# TK90X.net
KiCad netlist of a schematic drawn in EAGLE
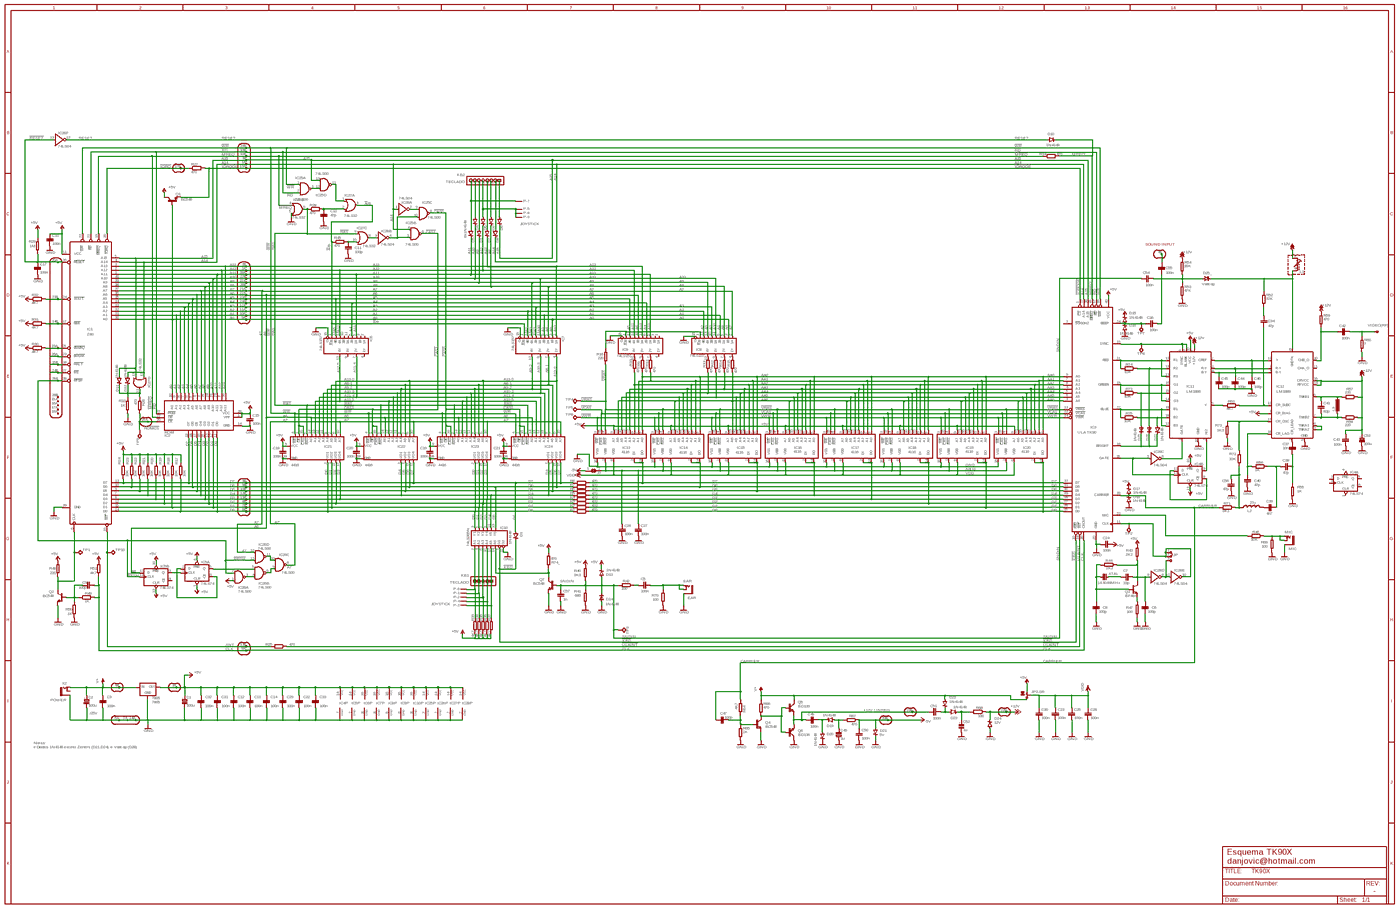
[diagram p0: schematic, sheet 1, overview]
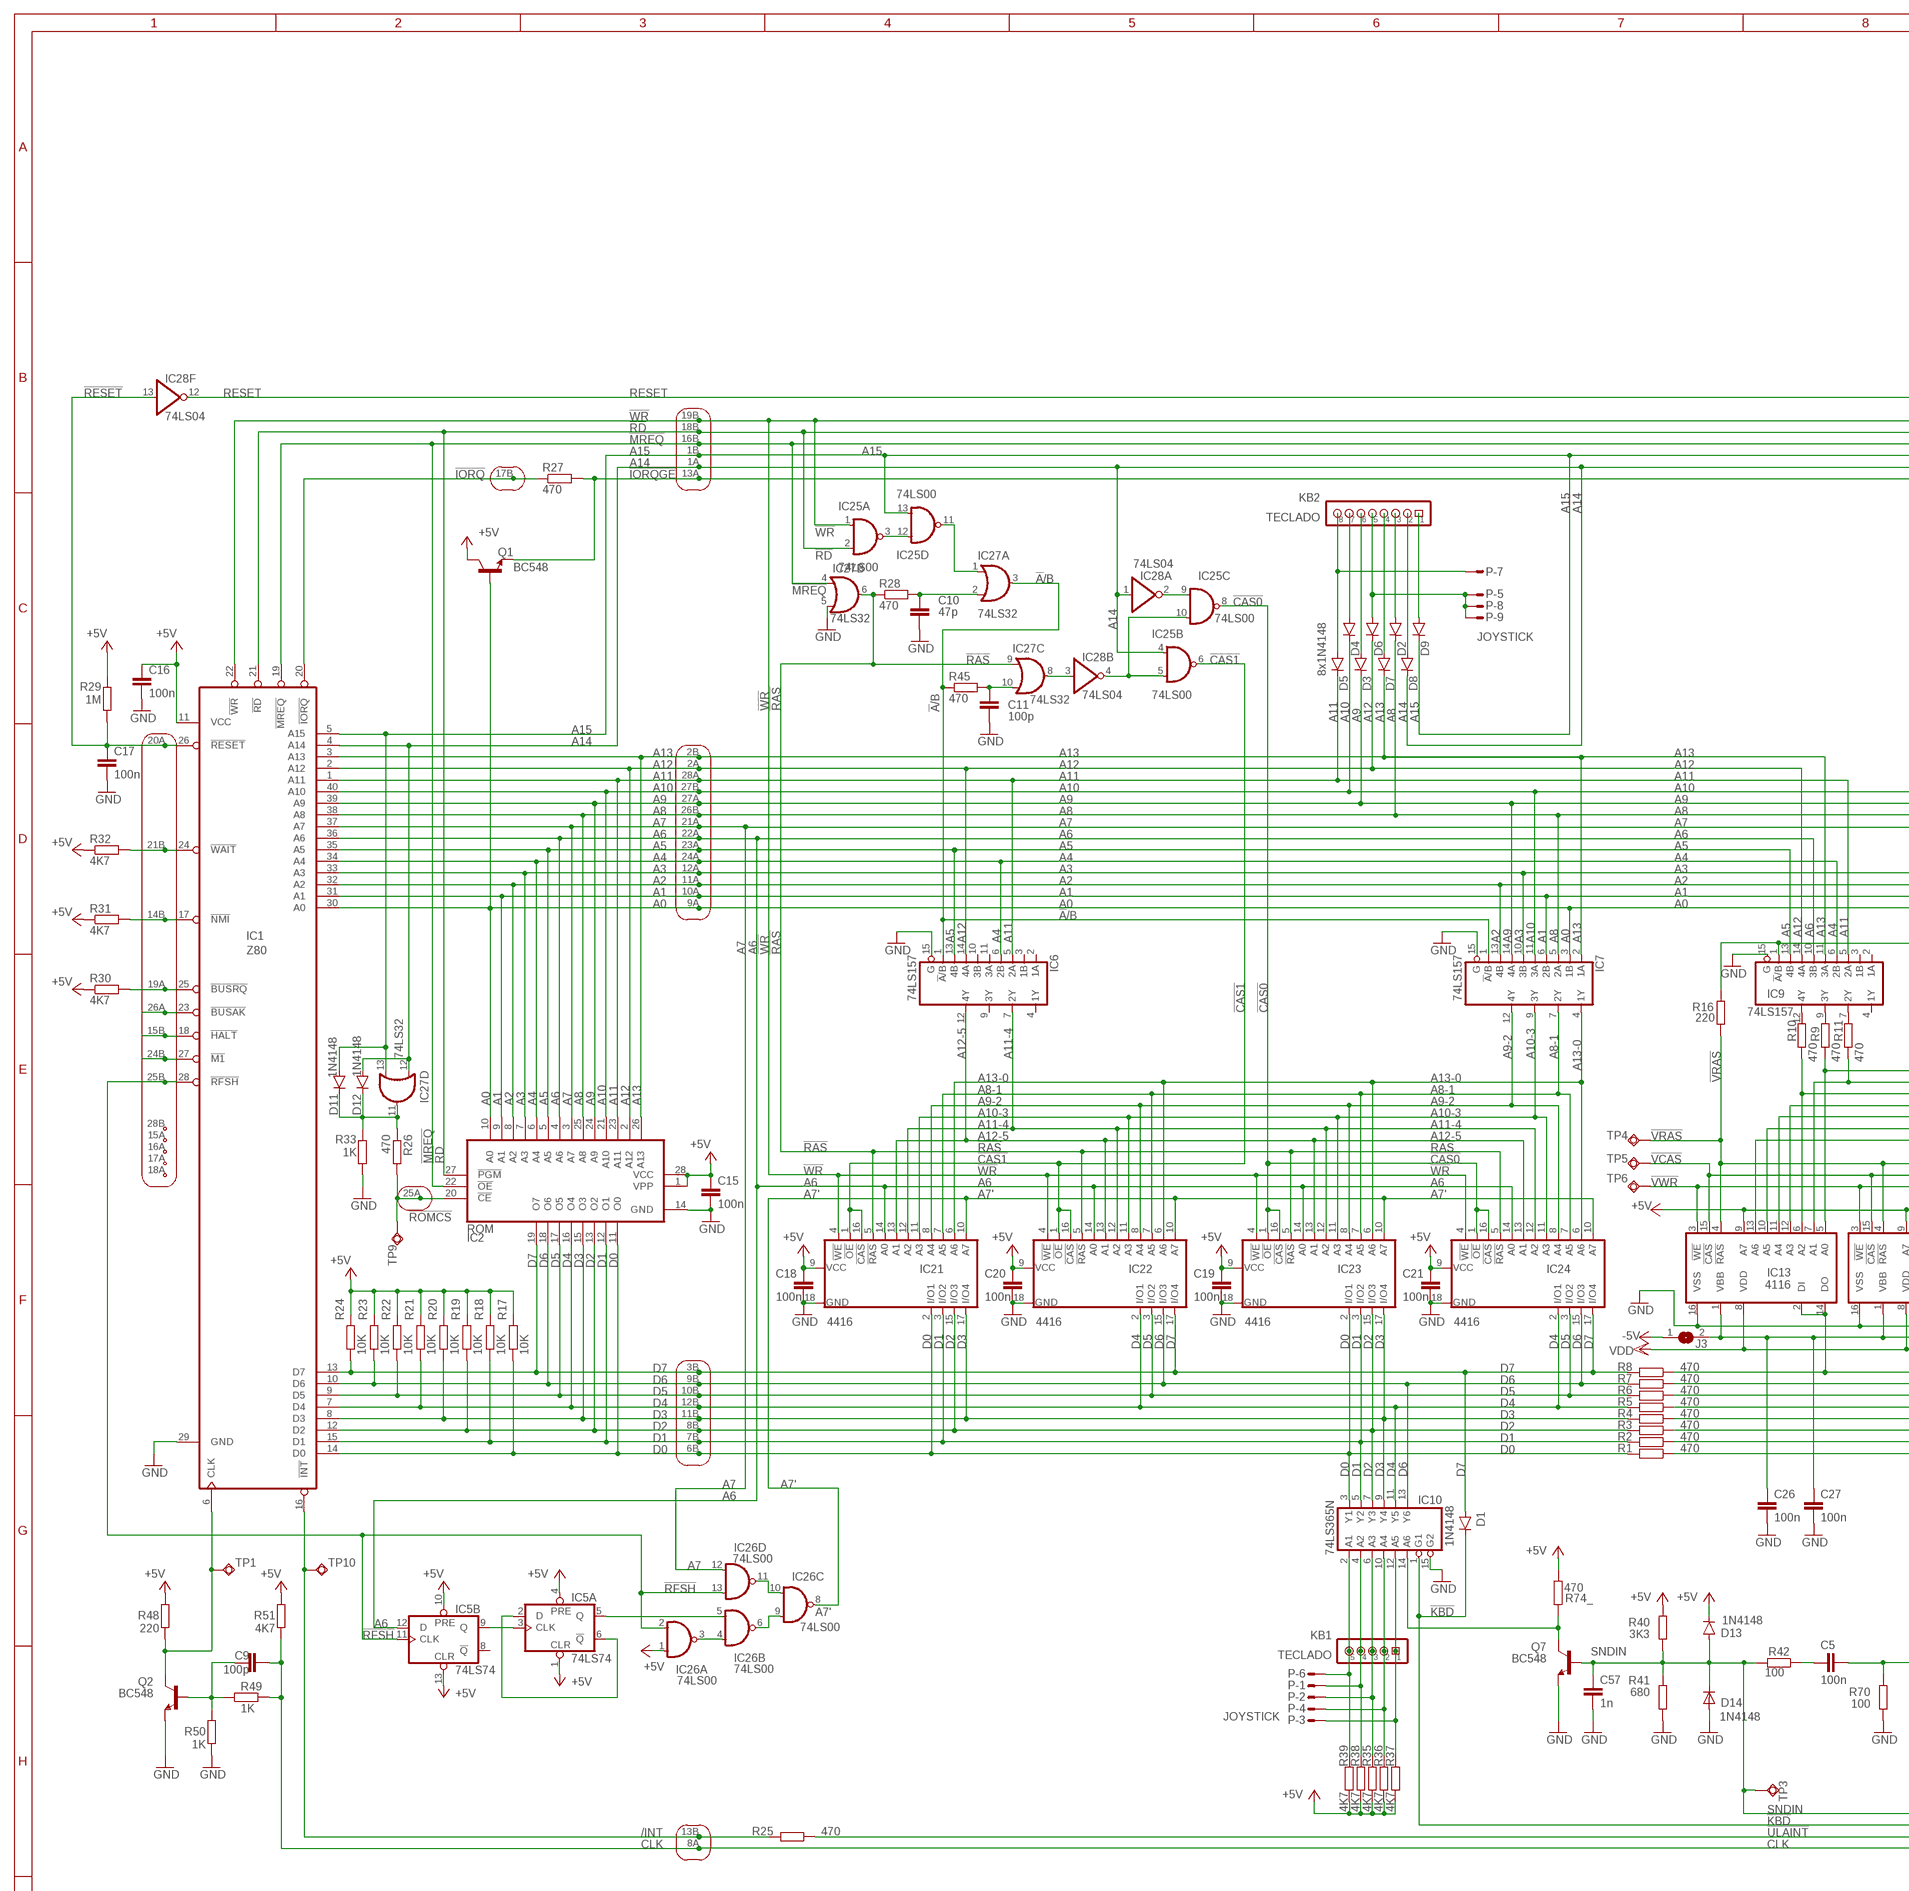
[diagram p1: schematic, sheet 1, part 1 of 4]
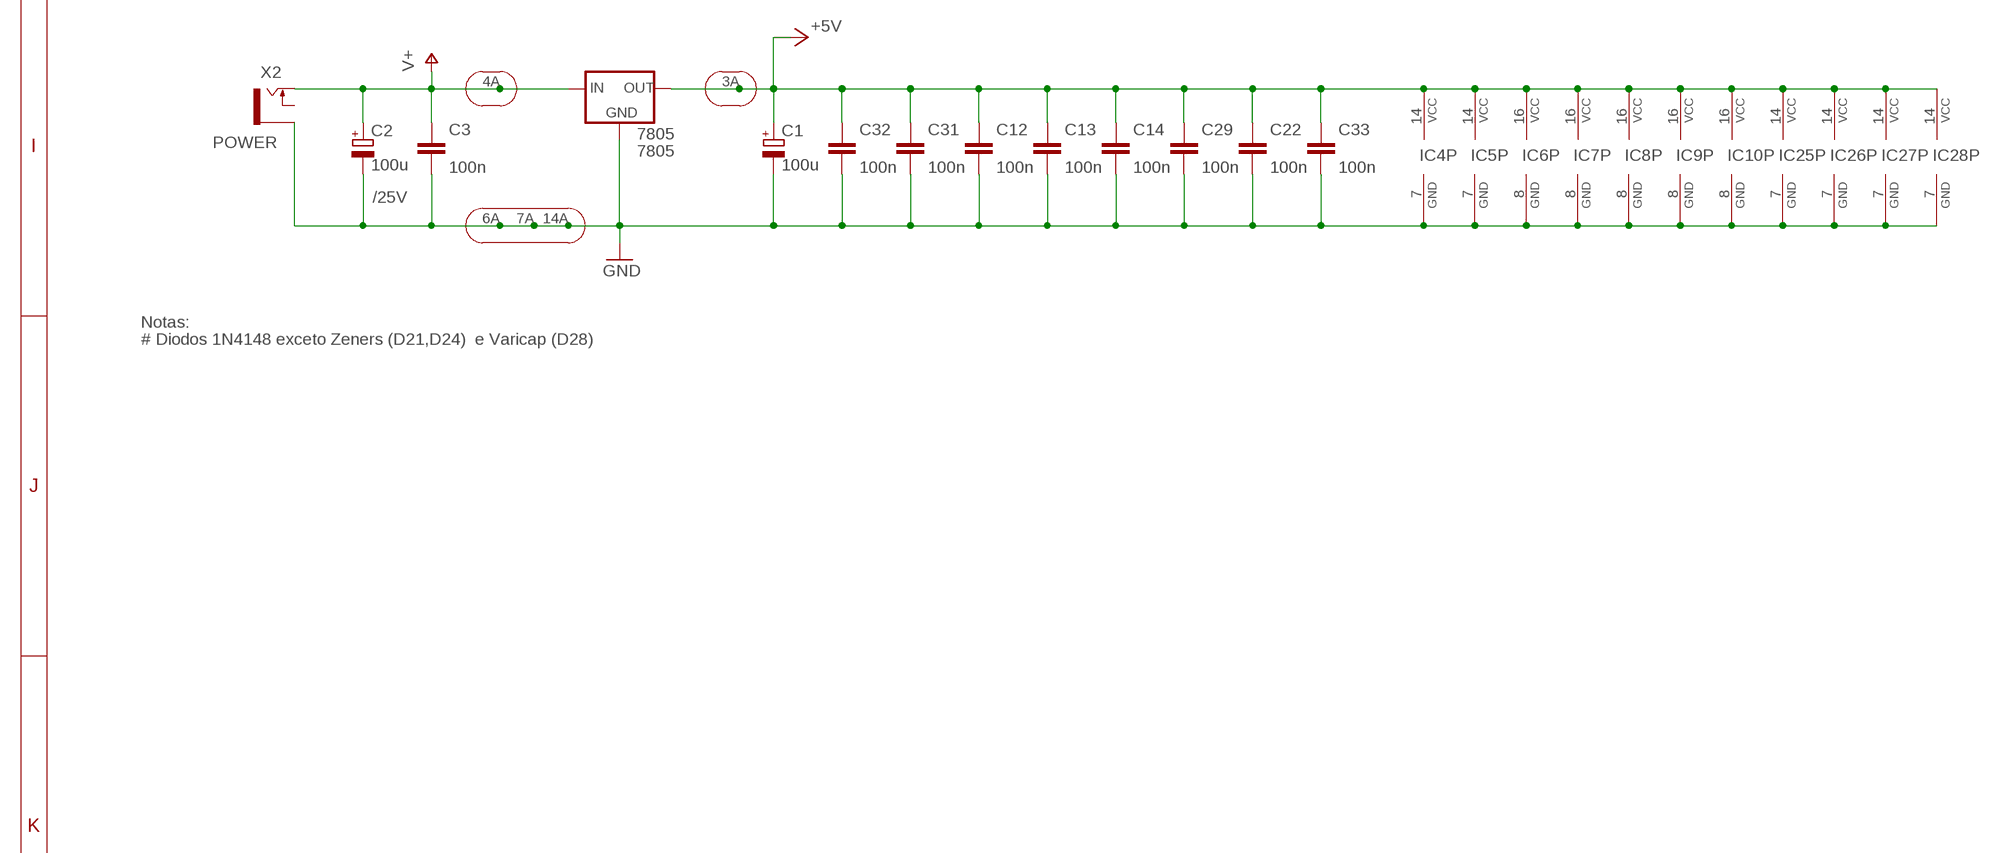
[diagram p2: schematic, sheet 1, part 2 of 4]
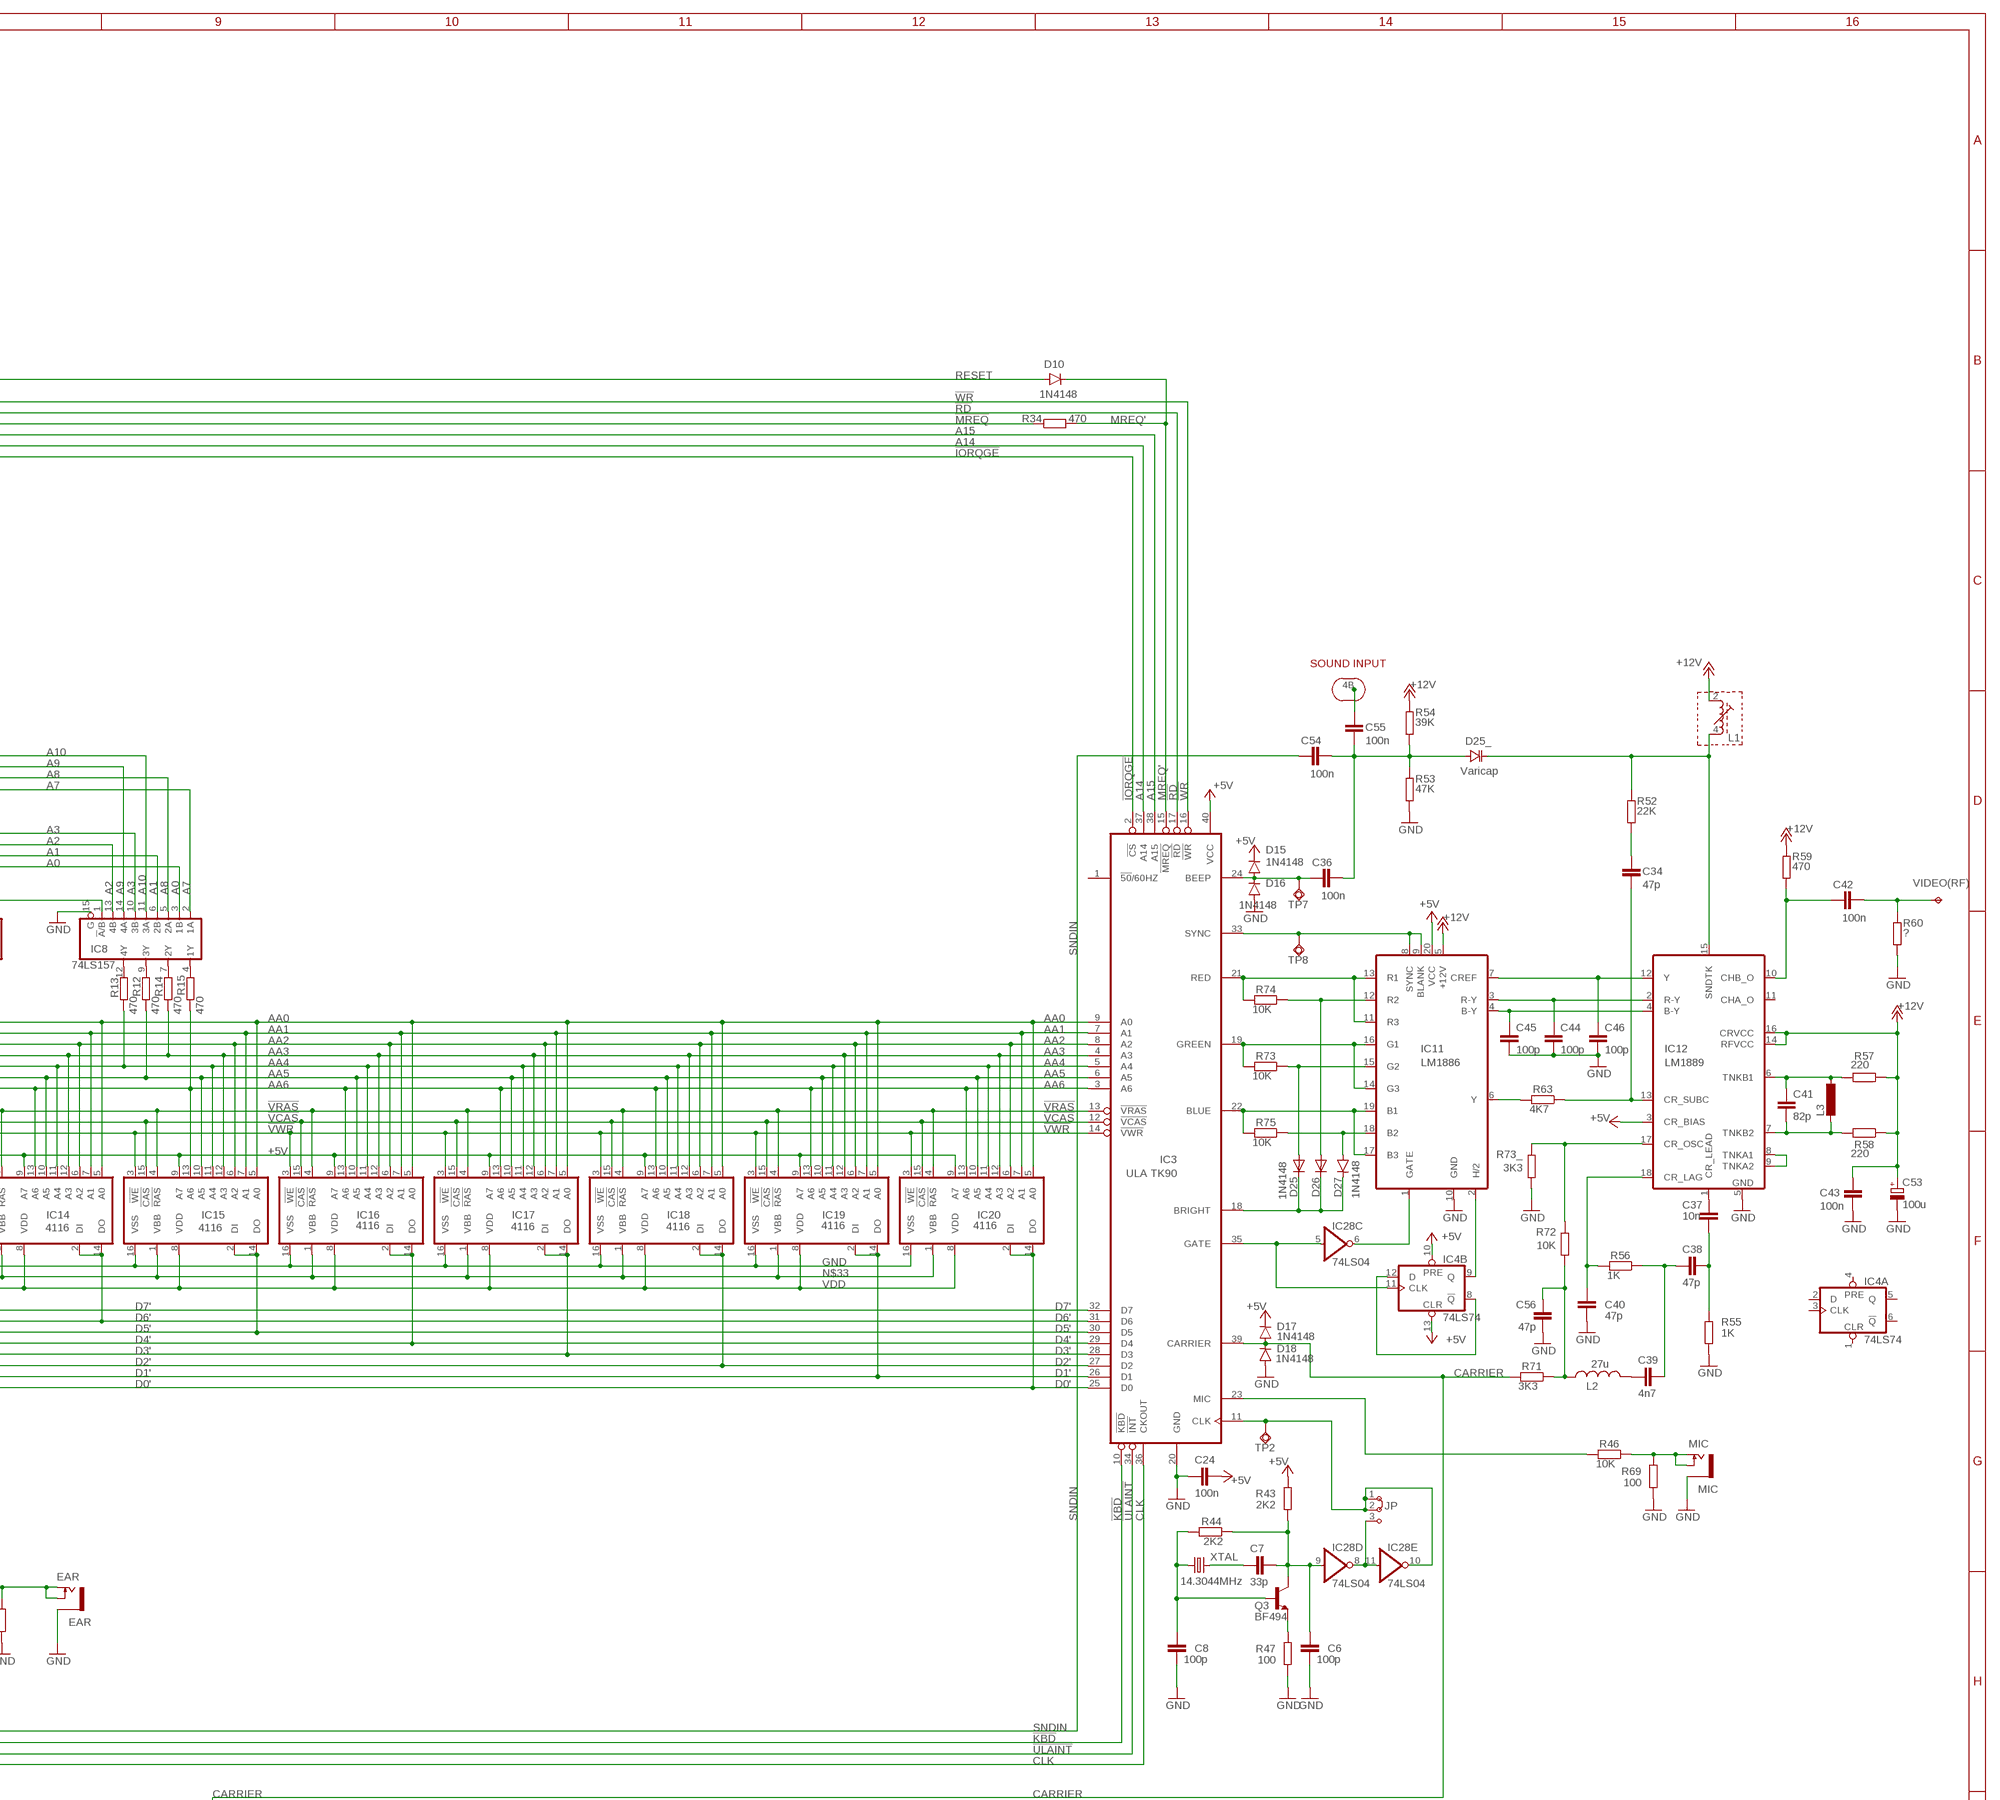
[diagram p3: schematic, sheet 1, part 3 of 4]
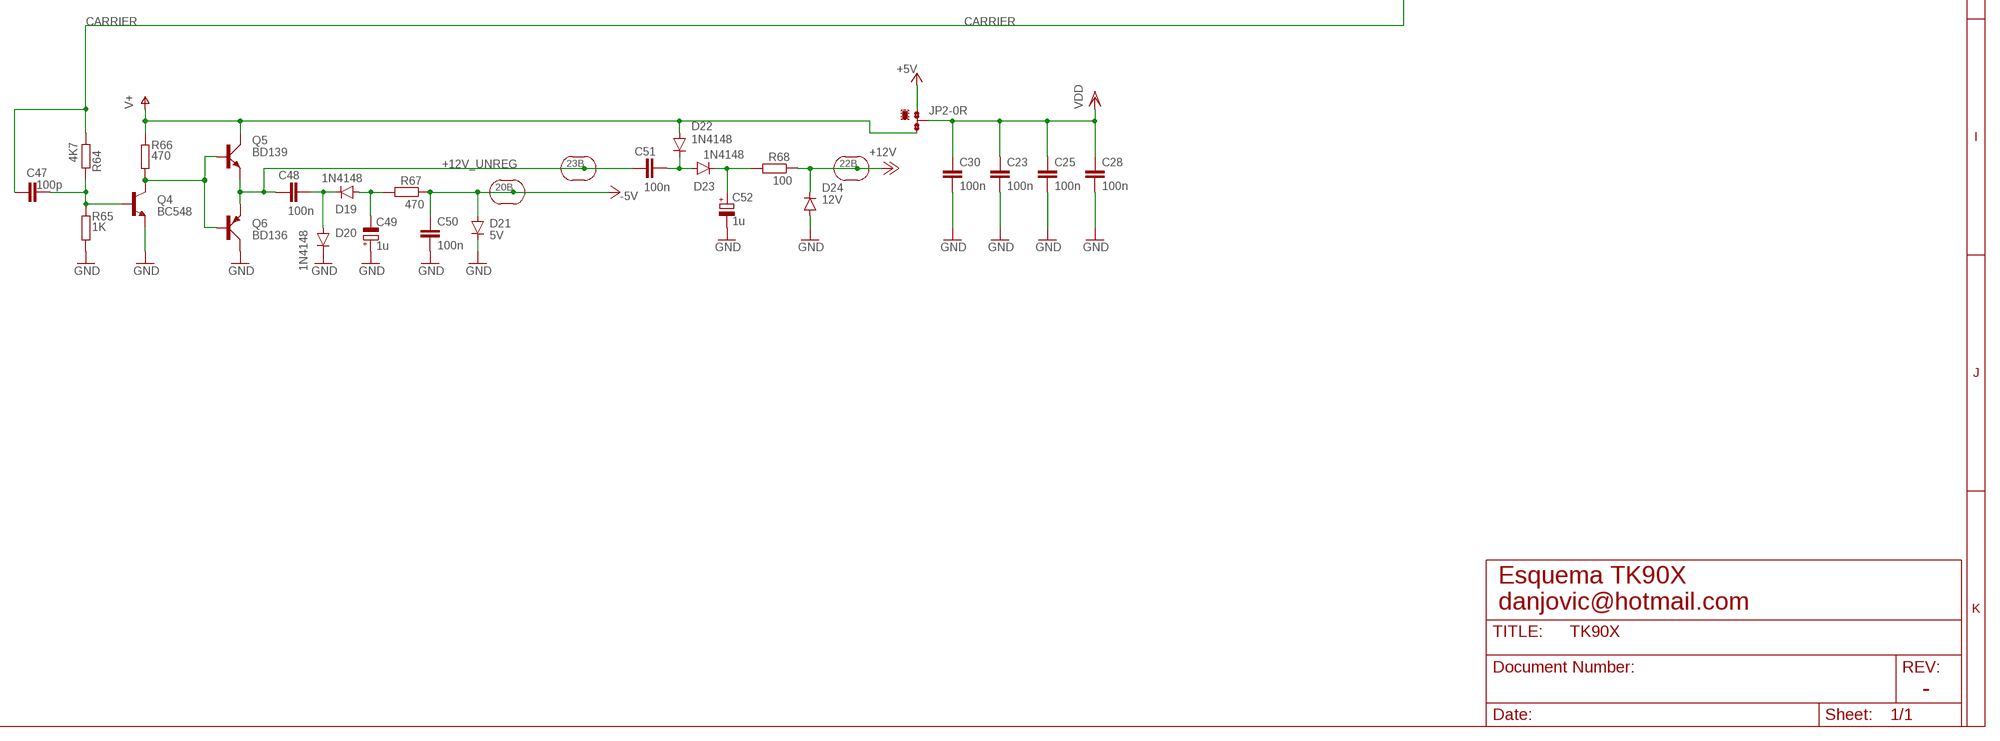
[diagram p4: schematic, sheet 1, part 4 of 4]

(export (version "E")
  (design (tool "Eeschema 10.0.6"))
  (components
    (comp (ref "7805")
      (value "7805")
      (footprint "eagle-import:78XXL")
      (libsource (lib "eagle-import") (part "78XXL"))
    )
    (comp (ref "C1")
      (value "100u")
      (footprint "eagle-import:E5-8,5")
      (libsource (lib "eagle-import") (part "CPOL-EUE5-8.5"))
    )
    (comp (ref "C2")
      (value "100u")
      (footprint "eagle-import:E5-8,5")
      (libsource (lib "eagle-import") (part "CPOL-EUE5-8.5"))
    )
    (comp (ref "C3")
      (value "100n")
      (footprint "eagle-import:C050-024X044")
      (libsource (lib "eagle-import") (part "C-EU050-024X044"))
    )
    (comp (ref "C5")
      (value "100n")
      (footprint "eagle-import:C050-024X044")
      (libsource (lib "eagle-import") (part "C-EU050-024X044"))
    )
    (comp (ref "C6")
      (value "100p")
      (footprint "eagle-import:C050-024X044")
      (libsource (lib "eagle-import") (part "C-EU050-024X044"))
    )
    (comp (ref "C7")
      (value "33p")
      (footprint "eagle-import:C050-024X044")
      (libsource (lib "eagle-import") (part "C-EU050-024X044"))
    )
    (comp (ref "C8")
      (value "100p")
      (footprint "eagle-import:C050-024X044")
      (libsource (lib "eagle-import") (part "C-EU050-024X044"))
    )
    (comp (ref "C9")
      (value "100p")
      (footprint "eagle-import:C050-024X044")
      (libsource (lib "eagle-import") (part "C-EU050-024X044"))
    )
    (comp (ref "C10")
      (value "47p")
      (footprint "eagle-import:C050-024X044")
      (libsource (lib "eagle-import") (part "C-EU050-024X044"))
    )
    (comp (ref "C11")
      (value "100p")
      (footprint "eagle-import:C050-024X044")
      (libsource (lib "eagle-import") (part "C-EU050-024X044"))
    )
    (comp (ref "C12")
      (value "100n")
      (footprint "eagle-import:C050-024X044")
      (libsource (lib "eagle-import") (part "C-EU050-024X044"))
    )
    (comp (ref "C13")
      (value "100n")
      (footprint "eagle-import:C050-024X044")
      (libsource (lib "eagle-import") (part "C-EU050-024X044"))
    )
    (comp (ref "C14")
      (value "100n")
      (footprint "eagle-import:C050-024X044")
      (libsource (lib "eagle-import") (part "C-EU050-024X044"))
    )
    (comp (ref "C15")
      (value "100n")
      (footprint "eagle-import:C050-024X044")
      (libsource (lib "eagle-import") (part "C-EU050-024X044"))
    )
    (comp (ref "C16")
      (value "100n")
      (footprint "eagle-import:C050-024X044")
      (libsource (lib "eagle-import") (part "C-EU050-024X044"))
    )
    (comp (ref "C17")
      (value "100n")
      (footprint "eagle-import:C050-024X044")
      (libsource (lib "eagle-import") (part "C-EU050-024X044"))
    )
    (comp (ref "C18")
      (value "100n")
      (footprint "eagle-import:C050-024X044")
      (libsource (lib "eagle-import") (part "C-EU050-024X044"))
    )
    (comp (ref "C19")
      (value "100n")
      (footprint "eagle-import:C050-024X044")
      (libsource (lib "eagle-import") (part "C-EU050-024X044"))
    )
    (comp (ref "C20")
      (value "100n")
      (footprint "eagle-import:C050-024X044")
      (libsource (lib "eagle-import") (part "C-EU050-024X044"))
    )
    (comp (ref "C21")
      (value "100n")
      (footprint "eagle-import:C050-024X044")
      (libsource (lib "eagle-import") (part "C-EU050-024X044"))
    )
    (comp (ref "C22")
      (value "100n")
      (footprint "eagle-import:C050-024X044")
      (libsource (lib "eagle-import") (part "C-EU050-024X044"))
    )
    (comp (ref "C23")
      (value "100n")
      (footprint "eagle-import:C050-024X044")
      (libsource (lib "eagle-import") (part "C-EU050-024X044"))
    )
    (comp (ref "C24")
      (value "100n")
      (footprint "eagle-import:C050-024X044")
      (libsource (lib "eagle-import") (part "C-EU050-024X044"))
    )
    (comp (ref "C25")
      (value "100n")
      (footprint "eagle-import:C050-024X044")
      (libsource (lib "eagle-import") (part "C-EU050-024X044"))
    )
    (comp (ref "C26")
      (value "100n")
      (footprint "eagle-import:C050-024X044")
      (libsource (lib "eagle-import") (part "C-EU050-024X044"))
    )
    (comp (ref "C27")
      (value "100n")
      (footprint "eagle-import:C050-024X044")
      (libsource (lib "eagle-import") (part "C-EU050-024X044"))
    )
    (comp (ref "C28")
      (value "100n")
      (footprint "eagle-import:C050-024X044")
      (libsource (lib "eagle-import") (part "C-EU050-024X044"))
    )
    (comp (ref "C29")
      (value "100n")
      (footprint "eagle-import:C050-024X044")
      (libsource (lib "eagle-import") (part "C-EU050-024X044"))
    )
    (comp (ref "C30")
      (value "100n")
      (footprint "eagle-import:C050-024X044")
      (libsource (lib "eagle-import") (part "C-EU050-024X044"))
    )
    (comp (ref "C31")
      (value "100n")
      (footprint "eagle-import:C050-024X044")
      (libsource (lib "eagle-import") (part "C-EU050-024X044"))
    )
    (comp (ref "C32")
      (value "100n")
      (footprint "eagle-import:C050-024X044")
      (libsource (lib "eagle-import") (part "C-EU050-024X044"))
    )
    (comp (ref "C33")
      (value "100n")
      (footprint "eagle-import:C050-024X044")
      (libsource (lib "eagle-import") (part "C-EU050-024X044"))
    )
    (comp (ref "C34")
      (value "47p")
      (footprint "eagle-import:C050-024X044")
      (libsource (lib "eagle-import") (part "C-EU050-024X044"))
    )
    (comp (ref "C36")
      (value "100n")
      (footprint "eagle-import:C050-024X044")
      (libsource (lib "eagle-import") (part "C-EU050-024X044"))
    )
    (comp (ref "C37")
      (value "10n")
      (footprint "eagle-import:C050-024X044")
      (libsource (lib "eagle-import") (part "C-EU050-024X044"))
    )
    (comp (ref "C38")
      (value "47p")
      (footprint "eagle-import:C050-024X044")
      (libsource (lib "eagle-import") (part "C-EU050-024X044"))
    )
    (comp (ref "C39")
      (value "4n7")
      (footprint "eagle-import:C050-024X044")
      (libsource (lib "eagle-import") (part "C-EU050-024X044"))
    )
    (comp (ref "C40")
      (value "47p")
      (footprint "eagle-import:C050-024X044")
      (libsource (lib "eagle-import") (part "C-EU050-024X044"))
    )
    (comp (ref "C41")
      (value "82p")
      (footprint "eagle-import:C050-024X044")
      (libsource (lib "eagle-import") (part "C-EU050-024X044"))
    )
    (comp (ref "C42")
      (value "100n")
      (footprint "eagle-import:C050-024X044")
      (libsource (lib "eagle-import") (part "C-EU050-024X044"))
    )
    (comp (ref "C43")
      (value "100n")
      (footprint "eagle-import:C050-024X044")
      (libsource (lib "eagle-import") (part "C-EU050-024X044"))
    )
    (comp (ref "C44")
      (value "100p")
      (footprint "eagle-import:C050-024X044")
      (libsource (lib "eagle-import") (part "C-EU050-024X044"))
    )
    (comp (ref "C45")
      (value "100p")
      (footprint "eagle-import:C050-024X044")
      (libsource (lib "eagle-import") (part "C-EU050-024X044"))
    )
    (comp (ref "C46")
      (value "100p")
      (footprint "eagle-import:C050-024X044")
      (libsource (lib "eagle-import") (part "C-EU050-024X044"))
    )
    (comp (ref "C47")
      (value "100p")
      (footprint "eagle-import:C050-024X044")
      (libsource (lib "eagle-import") (part "C-EU050-024X044"))
    )
    (comp (ref "C48")
      (value "100n")
      (footprint "eagle-import:C050-024X044")
      (libsource (lib "eagle-import") (part "C-EU050-024X044"))
    )
    (comp (ref "C49")
      (value "1u")
      (footprint "eagle-import:E2-4")
      (libsource (lib "eagle-import") (part "CPOL-EUE2-4"))
    )
    (comp (ref "C50")
      (value "100n")
      (footprint "eagle-import:C050-024X044")
      (libsource (lib "eagle-import") (part "C-EU050-024X044"))
    )
    (comp (ref "C51")
      (value "100n")
      (footprint "eagle-import:C050-024X044")
      (libsource (lib "eagle-import") (part "C-EU050-024X044"))
    )
    (comp (ref "C52")
      (value "1u")
      (footprint "eagle-import:E2-5")
      (libsource (lib "eagle-import") (part "CPOL-EUE2-5"))
    )
    (comp (ref "C53")
      (value "100u")
      (footprint "eagle-import:E5-4")
      (libsource (lib "eagle-import") (part "CPOL-EUE5-4"))
    )
    (comp (ref "C54")
      (value "100n")
      (footprint "eagle-import:C050-024X044")
      (libsource (lib "eagle-import") (part "C-EU050-024X044"))
    )
    (comp (ref "C55")
      (value "100n")
      (footprint "eagle-import:C050-024X044")
      (libsource (lib "eagle-import") (part "C-EU050-024X044"))
    )
    (comp (ref "C56")
      (value "47p")
      (footprint "eagle-import:C050-024X044")
      (libsource (lib "eagle-import") (part "C-EU050-024X044"))
    )
    (comp (ref "C57")
      (value "1n")
      (footprint "eagle-import:C050-024X044")
      (libsource (lib "eagle-import") (part "C-EU050-024X044"))
    )
    (comp (ref "D1")
      (value "1N4148")
      (footprint "eagle-import:DO35-12")
      (libsource (lib "eagle-import") (part "DDO35-12"))
    )
    (comp (ref "D2")
      (value "1N4148")
      (footprint "eagle-import:DO35-12")
      (libsource (lib "eagle-import") (part "DDO35-12"))
    )
    (comp (ref "D3")
      (value "1N4148")
      (footprint "eagle-import:DO35-12")
      (libsource (lib "eagle-import") (part "DDO35-12"))
    )
    (comp (ref "D4")
      (value "1N4148")
      (footprint "eagle-import:DO35-12")
      (libsource (lib "eagle-import") (part "DDO35-12"))
    )
    (comp (ref "D5")
      (value "1N4148")
      (footprint "eagle-import:DO35-12")
      (libsource (lib "eagle-import") (part "DDO35-12"))
    )
    (comp (ref "D6")
      (value "1N4148")
      (footprint "eagle-import:DO35-12")
      (libsource (lib "eagle-import") (part "DDO35-12"))
    )
    (comp (ref "D7")
      (value "1N4148")
      (footprint "eagle-import:DO35-12")
      (libsource (lib "eagle-import") (part "DDO35-12"))
    )
    (comp (ref "D8")
      (value "1N4148")
      (footprint "eagle-import:DO35-12")
      (libsource (lib "eagle-import") (part "DDO35-12"))
    )
    (comp (ref "D9")
      (value "1N4148")
      (footprint "eagle-import:DO35-12")
      (libsource (lib "eagle-import") (part "DDO35-12"))
    )
    (comp (ref "D10")
      (value "1N4148")
      (footprint "eagle-import:DO35-12")
      (libsource (lib "eagle-import") (part "DDO35-12"))
    )
    (comp (ref "D11")
      (value "1N4148")
      (footprint "eagle-import:DO35-12")
      (libsource (lib "eagle-import") (part "DDO35-12"))
    )
    (comp (ref "D12")
      (value "1N4148")
      (footprint "eagle-import:DO35-12")
      (libsource (lib "eagle-import") (part "DDO35-12"))
    )
    (comp (ref "D13")
      (value "1N4148")
      (footprint "eagle-import:DO35-12")
      (libsource (lib "eagle-import") (part "DDO35-12"))
    )
    (comp (ref "D14")
      (value "1N4148")
      (footprint "eagle-import:D-5")
      (libsource (lib "eagle-import") (part "DIODE-D-5"))
    )
    (comp (ref "D15")
      (value "1N4148")
      (footprint "eagle-import:DO35-12")
      (libsource (lib "eagle-import") (part "DDO35-12"))
    )
    (comp (ref "D16")
      (value "1N4148")
      (footprint "eagle-import:DO35-12")
      (libsource (lib "eagle-import") (part "DDO35-12"))
    )
    (comp (ref "D17")
      (value "1N4148")
      (footprint "eagle-import:DO35-12")
      (libsource (lib "eagle-import") (part "DDO35-12"))
    )
    (comp (ref "D18")
      (value "1N4148")
      (footprint "eagle-import:DO35-12")
      (libsource (lib "eagle-import") (part "DDO35-12"))
    )
    (comp (ref "D19")
      (value "1N4148")
      (footprint "eagle-import:DO35-12")
      (libsource (lib "eagle-import") (part "DDO35-12"))
    )
    (comp (ref "D20")
      (value "1N4148")
      (footprint "eagle-import:DO35-12")
      (libsource (lib "eagle-import") (part "DDO35-12"))
    )
    (comp (ref "D21")
      (value "5V")
      (footprint "eagle-import:DO35-12")
      (libsource (lib "eagle-import") (part "DDO35-12"))
    )
    (comp (ref "D22")
      (value "1N4148")
      (footprint "eagle-import:DO35-12")
      (libsource (lib "eagle-import") (part "DDO35-12"))
    )
    (comp (ref "D23")
      (value "1N4148")
      (footprint "eagle-import:DO35-12")
      (libsource (lib "eagle-import") (part "DDO35-12"))
    )
    (comp (ref "D24")
      (value "12V")
      (footprint "eagle-import:DO35-12")
      (libsource (lib "eagle-import") (part "DDO35-12"))
    )
    (comp (ref "D25")
      (value "1N4148")
      (footprint "eagle-import:D-5")
      (libsource (lib "eagle-import") (part "DIODE-D-5"))
    )
    (comp (ref "D25_")
      (value "Varicap")
      (footprint "eagle-import:D200")
      (libsource (lib "eagle-import") (part "VARICAP-200"))
    )
    (comp (ref "D26")
      (value "1N4148")
      (footprint "eagle-import:D-5")
      (libsource (lib "eagle-import") (part "DIODE-D-5"))
    )
    (comp (ref "D27")
      (value "1N4148")
      (footprint "eagle-import:DO35-12")
      (libsource (lib "eagle-import") (part "DDO35-12"))
    )
    (comp (ref "EAR")
      (value "EAR")
      (footprint "eagle-import:MONO")
      (libsource (lib "eagle-import") (part "JACK?-MONO"))
    )
    (comp (ref "IC1")
      (value "Z80")
      (footprint "eagle-import:DIL40")
      (libsource (lib "eagle-import") (part "Z80CPU"))
    )
    (comp (ref "IC2")
      (value "ROM")
      (footprint "eagle-import:DIL28")
      (libsource (lib "eagle-import") (part "25128"))
    )
    (comp (ref "IC3")
      (value "ULA TK90")
      (footprint "eagle-import:DIL40")
      (libsource (lib "eagle-import") (part "ULA-TK90"))
    )
    (comp (ref "IC4")
      (value "74LS74")
      (footprint "eagle-import:DIL14")
      (libsource (lib "eagle-import") (part "7474NLS"))
    )
    (comp (ref "IC5")
      (value "74LS74")
      (footprint "eagle-import:DIL14")
      (libsource (lib "eagle-import") (part "7474NLS"))
    )
    (comp (ref "IC6")
      (value "74LS157")
      (footprint "eagle-import:DIL16")
      (libsource (lib "eagle-import") (part "74157NS"))
    )
    (comp (ref "IC7")
      (value "74LS157")
      (footprint "eagle-import:DIL16")
      (libsource (lib "eagle-import") (part "74157NS"))
    )
    (comp (ref "IC8")
      (value "74LS157")
      (footprint "eagle-import:DIL16")
      (libsource (lib "eagle-import") (part "74157NS"))
    )
    (comp (ref "IC9")
      (value "74LS157")
      (footprint "eagle-import:DIL16")
      (libsource (lib "eagle-import") (part "74157NS"))
    )
    (comp (ref "IC10")
      (value "74LS365N")
      (footprint "eagle-import:DIL16")
      (libsource (lib "eagle-import") (part "74365NLS"))
    )
    (comp (ref "IC11")
      (value "LM1886")
      (footprint "eagle-import:DIL20")
      (libsource (lib "eagle-import") (part "LM1886N"))
    )
    (comp (ref "IC12")
      (value "LM1889")
      (footprint "eagle-import:DIL18")
      (libsource (lib "eagle-import") (part "LM1889"))
    )
    (comp (ref "IC13")
      (value "4116")
      (footprint "eagle-import:DIL16")
      (libsource (lib "eagle-import") (part "MK4516"))
    )
    (comp (ref "IC14")
      (value "4116")
      (footprint "eagle-import:DIL16")
      (libsource (lib "eagle-import") (part "MK4516"))
    )
    (comp (ref "IC15")
      (value "4116")
      (footprint "eagle-import:DIL16")
      (libsource (lib "eagle-import") (part "MK4516"))
    )
    (comp (ref "IC16")
      (value "4116")
      (footprint "eagle-import:DIL16")
      (libsource (lib "eagle-import") (part "MK4516"))
    )
    (comp (ref "IC17")
      (value "4116")
      (footprint "eagle-import:DIL16")
      (libsource (lib "eagle-import") (part "MK4516"))
    )
    (comp (ref "IC18")
      (value "4116")
      (footprint "eagle-import:DIL16")
      (libsource (lib "eagle-import") (part "MK4516"))
    )
    (comp (ref "IC19")
      (value "4116")
      (footprint "eagle-import:DIL16")
      (libsource (lib "eagle-import") (part "MK4516"))
    )
    (comp (ref "IC20")
      (value "4116")
      (footprint "eagle-import:DIL16")
      (libsource (lib "eagle-import") (part "MK4516"))
    )
    (comp (ref "IC21")
      (value "4416")
      (footprint "eagle-import:DIL18")
      (libsource (lib "eagle-import") (part "4416"))
    )
    (comp (ref "IC22")
      (value "4416")
      (footprint "eagle-import:DIL18")
      (libsource (lib "eagle-import") (part "4416"))
    )
    (comp (ref "IC23")
      (value "4416")
      (footprint "eagle-import:DIL18")
      (libsource (lib "eagle-import") (part "4416"))
    )
    (comp (ref "IC24")
      (value "4416")
      (footprint "eagle-import:DIL18")
      (libsource (lib "eagle-import") (part "4416"))
    )
    (comp (ref "IC25")
      (value "74LS00")
      (footprint "eagle-import:DIL14")
      (libsource (lib "eagle-import") (part "7400NLS"))
    )
    (comp (ref "IC26")
      (value "74LS00")
      (footprint "eagle-import:DIL14")
      (libsource (lib "eagle-import") (part "7400NLS"))
    )
    (comp (ref "IC27")
      (value "74LS32")
      (footprint "eagle-import:DIL14")
      (libsource (lib "eagle-import") (part "7432NLS"))
    )
    (comp (ref "IC28")
      (value "74LS04")
      (footprint "eagle-import:DIL14")
      (libsource (lib "eagle-import") (part "7404NLS"))
    )
    (comp (ref "J3") (value "SJ") (footprint "eagle-import:SJ") (libsource (lib "eagle-import") (part "SJ")))
    (comp (ref "JP")
      (value "J2X1MM")
      (footprint "eagle-import:03C")
      (libsource (lib "eagle-import") (part "J2X1MM"))
    )
    (comp (ref "JP2")
      (value "0R-JUMPB")
      (footprint "eagle-import:B0R-JMP")
      (libsource (lib "eagle-import") (part "0R-JUMPB"))
    )
    (comp (ref "KB1")
      (value "TECLADO")
      (footprint "eagle-import:FE05-1")
      (libsource (lib "eagle-import") (part "CON-TECL-5"))
    )
    (comp (ref "KB2")
      (value "TECLADO")
      (footprint "eagle-import:FE08")
      (libsource (lib "eagle-import") (part "CON-TECL-8"))
    )
    (comp (ref "L1")
      (value "COIL")
      (footprint "eagle-import:COIL")
      (libsource (lib "eagle-import") (part "COIL"))
    )
    (comp (ref "L2")
      (value "27u")
      (footprint "eagle-import:0207_7")
      (libsource (lib "eagle-import") (part "L-US0207/7"))
    )
    (comp (ref "L3")
      (value "L-EU0204/5")
      (footprint "eagle-import:0204_5")
      (libsource (lib "eagle-import") (part "L-EU0204/5"))
    )
    (comp (ref "MIC")
      (value "MIC")
      (footprint "eagle-import:MONO")
      (libsource (lib "eagle-import") (part "JACK?-MONO"))
    )
    (comp (ref "P")
      (value "JOYSTICK")
      (footprint "eagle-import:177-009-MALE")
      (libsource (lib "eagle-import") (part "M09?S.590"))
    )
    (comp (ref "Q1")
      (value "BC548")
      (footprint "eagle-import:TO92L")
      (libsource (lib "eagle-import") (part "-NPN-TO92L"))
    )
    (comp (ref "Q2")
      (value "BC548")
      (footprint "eagle-import:TO92L")
      (libsource (lib "eagle-import") (part "-NPN-TO92L"))
    )
    (comp (ref "Q3")
      (value "BF494")
      (footprint "eagle-import:TO92-CEB")
      (libsource (lib "eagle-import") (part "BF494"))
    )
    (comp (ref "Q4")
      (value "BC548")
      (footprint "eagle-import:TO92L")
      (libsource (lib "eagle-import") (part "-NPN-TO92L"))
    )
    (comp (ref "Q5")
      (value "BD139")
      (footprint "eagle-import:TO126AV")
      (libsource (lib "eagle-import") (part "BD139"))
    )
    (comp (ref "Q6")
      (value "BD136")
      (footprint "eagle-import:TO126AV")
      (libsource (lib "eagle-import") (part "BD140"))
    )
    (comp (ref "Q7")
      (value "BC548")
      (footprint "eagle-import:TO92L")
      (libsource (lib "eagle-import") (part "-NPN-TO92L"))
    )
    (comp (ref "R1")
      (value "470")
      (footprint "eagle-import:0207_12")
      (libsource (lib "eagle-import") (part "R-EU_0207/12"))
    )
    (comp (ref "R2")
      (value "470")
      (footprint "eagle-import:0207_12")
      (libsource (lib "eagle-import") (part "R-EU_0207/12"))
    )
    (comp (ref "R3")
      (value "470")
      (footprint "eagle-import:0207_12")
      (libsource (lib "eagle-import") (part "R-EU_0207/12"))
    )
    (comp (ref "R4")
      (value "470")
      (footprint "eagle-import:0207_12")
      (libsource (lib "eagle-import") (part "R-EU_0207/12"))
    )
    (comp (ref "R5")
      (value "470")
      (footprint "eagle-import:0207_12")
      (libsource (lib "eagle-import") (part "R-EU_0207/12"))
    )
    (comp (ref "R6")
      (value "470")
      (footprint "eagle-import:0207_12")
      (libsource (lib "eagle-import") (part "R-EU_0207/12"))
    )
    (comp (ref "R7")
      (value "470")
      (footprint "eagle-import:0207_12")
      (libsource (lib "eagle-import") (part "R-EU_0207/12"))
    )
    (comp (ref "R8")
      (value "470")
      (footprint "eagle-import:0207_12")
      (libsource (lib "eagle-import") (part "R-EU_0207/12"))
    )
    (comp (ref "R9")
      (value "470")
      (footprint "eagle-import:0207_12")
      (libsource (lib "eagle-import") (part "R-EU_0207/12"))
    )
    (comp (ref "R10")
      (value "470")
      (footprint "eagle-import:0207_12")
      (libsource (lib "eagle-import") (part "R-EU_0207/12"))
    )
    (comp (ref "R11")
      (value "470")
      (footprint "eagle-import:0207_12")
      (libsource (lib "eagle-import") (part "R-EU_0207/12"))
    )
    (comp (ref "R12")
      (value "470")
      (footprint "eagle-import:0207_12")
      (libsource (lib "eagle-import") (part "R-EU_0207/12"))
    )
    (comp (ref "R13")
      (value "470")
      (footprint "eagle-import:0207_12")
      (libsource (lib "eagle-import") (part "R-EU_0207/12"))
    )
    (comp (ref "R14")
      (value "470")
      (footprint "eagle-import:0207_12")
      (libsource (lib "eagle-import") (part "R-EU_0207/12"))
    )
    (comp (ref "R15")
      (value "470")
      (footprint "eagle-import:0207_12")
      (libsource (lib "eagle-import") (part "R-EU_0207/12"))
    )
    (comp (ref "R16")
      (value "220")
      (footprint "eagle-import:0207_12")
      (libsource (lib "eagle-import") (part "R-EU_0207/12"))
    )
    (comp (ref "R17")
      (value "10K")
      (footprint "eagle-import:0207_12")
      (libsource (lib "eagle-import") (part "R-EU_0207/12"))
    )
    (comp (ref "R18")
      (value "10K")
      (footprint "eagle-import:0207_12")
      (libsource (lib "eagle-import") (part "R-EU_0207/12"))
    )
    (comp (ref "R19")
      (value "10K")
      (footprint "eagle-import:0207_12")
      (libsource (lib "eagle-import") (part "R-EU_0207/12"))
    )
    (comp (ref "R20")
      (value "10K")
      (footprint "eagle-import:0207_12")
      (libsource (lib "eagle-import") (part "R-EU_0207/12"))
    )
    (comp (ref "R21")
      (value "10K")
      (footprint "eagle-import:0207_12")
      (libsource (lib "eagle-import") (part "R-EU_0207/12"))
    )
    (comp (ref "R22")
      (value "10K")
      (footprint "eagle-import:0207_12")
      (libsource (lib "eagle-import") (part "R-EU_0207/12"))
    )
    (comp (ref "R23")
      (value "10K")
      (footprint "eagle-import:0207_12")
      (libsource (lib "eagle-import") (part "R-EU_0207/12"))
    )
    (comp (ref "R24")
      (value "10K")
      (footprint "eagle-import:0207_12")
      (libsource (lib "eagle-import") (part "R-EU_0207/12"))
    )
    (comp (ref "R25")
      (value "470")
      (footprint "eagle-import:0207_12")
      (libsource (lib "eagle-import") (part "R-EU_0207/12"))
    )
    (comp (ref "R26")
      (value "470")
      (footprint "eagle-import:0207_12")
      (libsource (lib "eagle-import") (part "R-EU_0207/12"))
    )
    (comp (ref "R27")
      (value "470")
      (footprint "eagle-import:0207_12")
      (libsource (lib "eagle-import") (part "R-EU_0207/12"))
    )
    (comp (ref "R28")
      (value "470")
      (footprint "eagle-import:0207_12")
      (libsource (lib "eagle-import") (part "R-EU_0207/12"))
    )
    (comp (ref "R29")
      (value "1M")
      (footprint "eagle-import:0207_12")
      (libsource (lib "eagle-import") (part "R-EU_0207/12"))
    )
    (comp (ref "R30")
      (value "4K7")
      (footprint "eagle-import:0207_12")
      (libsource (lib "eagle-import") (part "R-EU_0207/12"))
    )
    (comp (ref "R31")
      (value "4K7")
      (footprint "eagle-import:0207_12")
      (libsource (lib "eagle-import") (part "R-EU_0207/12"))
    )
    (comp (ref "R32")
      (value "4K7")
      (footprint "eagle-import:0207_12")
      (libsource (lib "eagle-import") (part "R-EU_0207/12"))
    )
    (comp (ref "R33")
      (value "1K")
      (footprint "eagle-import:0207_12")
      (libsource (lib "eagle-import") (part "R-EU_0207/12"))
    )
    (comp (ref "R34")
      (value "470")
      (footprint "eagle-import:0207_12")
      (libsource (lib "eagle-import") (part "R-EU_0207/12"))
    )
    (comp (ref "R35")
      (value "4K7")
      (footprint "eagle-import:0207_12")
      (libsource (lib "eagle-import") (part "R-EU_0207/12"))
    )
    (comp (ref "R36")
      (value "4K7")
      (footprint "eagle-import:0207_12")
      (libsource (lib "eagle-import") (part "R-EU_0207/12"))
    )
    (comp (ref "R37")
      (value "4K7")
      (footprint "eagle-import:0207_12")
      (libsource (lib "eagle-import") (part "R-EU_0207/12"))
    )
    (comp (ref "R38")
      (value "4K7")
      (footprint "eagle-import:0207_12")
      (libsource (lib "eagle-import") (part "R-EU_0207/12"))
    )
    (comp (ref "R39")
      (value "4K7")
      (footprint "eagle-import:0207_12")
      (libsource (lib "eagle-import") (part "R-EU_0207/12"))
    )
    (comp (ref "R40")
      (value "3K3")
      (footprint "eagle-import:0207_12")
      (libsource (lib "eagle-import") (part "R-EU_0207/12"))
    )
    (comp (ref "R41")
      (value "680")
      (footprint "eagle-import:0207_5V")
      (libsource (lib "eagle-import") (part "R-EU_0207/5V"))
    )
    (comp (ref "R42")
      (value "100")
      (footprint "eagle-import:0207_5V")
      (libsource (lib "eagle-import") (part "R-EU_0207/5V"))
    )
    (comp (ref "R43")
      (value "2K2")
      (footprint "eagle-import:0207_12")
      (libsource (lib "eagle-import") (part "R-EU_0207/12"))
    )
    (comp (ref "R44")
      (value "2K2")
      (footprint "eagle-import:0207_12")
      (libsource (lib "eagle-import") (part "R-EU_0207/12"))
    )
    (comp (ref "R45")
      (value "470")
      (footprint "eagle-import:0207_12")
      (libsource (lib "eagle-import") (part "R-EU_0207/12"))
    )
    (comp (ref "R46")
      (value "10K")
      (footprint "eagle-import:0207_12")
      (libsource (lib "eagle-import") (part "R-EU_0207/12"))
    )
    (comp (ref "R47")
      (value "100")
      (footprint "eagle-import:0207_12")
      (libsource (lib "eagle-import") (part "R-EU_0207/12"))
    )
    (comp (ref "R48")
      (value "220")
      (footprint "eagle-import:0207_12")
      (libsource (lib "eagle-import") (part "R-EU_0207/12"))
    )
    (comp (ref "R49")
      (value "1K")
      (footprint "eagle-import:0207_12")
      (libsource (lib "eagle-import") (part "R-EU_0207/12"))
    )
    (comp (ref "R50")
      (value "1K")
      (footprint "eagle-import:0207_12")
      (libsource (lib "eagle-import") (part "R-EU_0207/12"))
    )
    (comp (ref "R51")
      (value "4K7")
      (footprint "eagle-import:0207_12")
      (libsource (lib "eagle-import") (part "R-EU_0207/12"))
    )
    (comp (ref "R52")
      (value "22K")
      (footprint "eagle-import:0207_5V")
      (libsource (lib "eagle-import") (part "R-EU_0207/5V"))
    )
    (comp (ref "R53")
      (value "47K")
      (footprint "eagle-import:0207_12")
      (libsource (lib "eagle-import") (part "R-EU_0207/12"))
    )
    (comp (ref "R54")
      (value "39K")
      (footprint "eagle-import:0207_12")
      (libsource (lib "eagle-import") (part "R-EU_0207/12"))
    )
    (comp (ref "R55")
      (value "1K")
      (footprint "eagle-import:0207_5V")
      (libsource (lib "eagle-import") (part "R-EU_0207/5V"))
    )
    (comp (ref "R56")
      (value "1K")
      (footprint "eagle-import:0207_5V")
      (libsource (lib "eagle-import") (part "R-EU_0207/5V"))
    )
    (comp (ref "R57")
      (value "220")
      (footprint "eagle-import:0207_5V")
      (libsource (lib "eagle-import") (part "R-EU_0207/5V"))
    )
    (comp (ref "R58")
      (value "220")
      (footprint "eagle-import:0207_5V")
      (libsource (lib "eagle-import") (part "R-EU_0207/5V"))
    )
    (comp (ref "R59")
      (value "470")
      (footprint "eagle-import:0207_5V")
      (libsource (lib "eagle-import") (part "R-EU_0207/5V"))
    )
    (comp (ref "R60")
      (value "?")
      (footprint "eagle-import:0207_5V")
      (libsource (lib "eagle-import") (part "R-EU_0207/5V"))
    )
    (comp (ref "R63")
      (value "4K7")
      (footprint "eagle-import:0207_12")
      (libsource (lib "eagle-import") (part "R-EU_0207/12"))
    )
    (comp (ref "R64")
      (value "4K7")
      (footprint "eagle-import:0207_12")
      (libsource (lib "eagle-import") (part "R-EU_0207/12"))
    )
    (comp (ref "R65")
      (value "1K")
      (footprint "eagle-import:0207_12")
      (libsource (lib "eagle-import") (part "R-EU_0207/12"))
    )
    (comp (ref "R66")
      (value "470")
      (footprint "eagle-import:0207_12")
      (libsource (lib "eagle-import") (part "R-EU_0207/12"))
    )
    (comp (ref "R67")
      (value "470")
      (footprint "eagle-import:0207_12")
      (libsource (lib "eagle-import") (part "R-EU_0207/12"))
    )
    (comp (ref "R68")
      (value "100")
      (footprint "eagle-import:0207_12")
      (libsource (lib "eagle-import") (part "R-EU_0207/12"))
    )
    (comp (ref "R69")
      (value "100")
      (footprint "eagle-import:0207_5V")
      (libsource (lib "eagle-import") (part "R-EU_0207/5V"))
    )
    (comp (ref "R70")
      (value "100")
      (footprint "eagle-import:0207_5V")
      (libsource (lib "eagle-import") (part "R-EU_0207/5V"))
    )
    (comp (ref "R71")
      (value "3K3")
      (footprint "eagle-import:0207_5V")
      (libsource (lib "eagle-import") (part "R-EU_0207/5V"))
    )
    (comp (ref "R72")
      (value "10K")
      (footprint "eagle-import:0207_5V")
      (libsource (lib "eagle-import") (part "R-EU_0207/5V"))
    )
    (comp (ref "R73")
      (value "10K")
      (footprint "eagle-import:0207_5V")
      (libsource (lib "eagle-import") (part "R-EU_0207/5V"))
    )
    (comp (ref "R73_")
      (value "3K3")
      (footprint "eagle-import:0207_12")
      (libsource (lib "eagle-import") (part "R-EU_0207/12"))
    )
    (comp (ref "R74")
      (value "10K")
      (footprint "eagle-import:0207_5V")
      (libsource (lib "eagle-import") (part "R-EU_0207/5V"))
    )
    (comp (ref "R74_")
      (value "470")
      (footprint "eagle-import:0207_12")
      (libsource (lib "eagle-import") (part "R-EU_0207/12"))
    )
    (comp (ref "R75")
      (value "10K")
      (footprint "eagle-import:0207_12")
      (libsource (lib "eagle-import") (part "R-EU_0207/12"))
    )
    (comp (ref "TP1")
      (value "TPSQPAD1-13")
      (footprint "eagle-import:P1-13")
      (libsource (lib "eagle-import") (part "TPSQPAD1-13"))
    )
    (comp (ref "TP2")
      (value "TPSQPAD1-13")
      (footprint "eagle-import:P1-13")
      (libsource (lib "eagle-import") (part "TPSQPAD1-13"))
    )
    (comp (ref "TP3")
      (value "TPSQPAD1-13")
      (footprint "eagle-import:P1-13")
      (libsource (lib "eagle-import") (part "TPSQPAD1-13"))
    )
    (comp (ref "TP4")
      (value "TPSQPAD1-13")
      (footprint "eagle-import:P1-13")
      (libsource (lib "eagle-import") (part "TPSQPAD1-13"))
    )
    (comp (ref "TP5")
      (value "TPSQPAD1-13")
      (footprint "eagle-import:P1-13")
      (libsource (lib "eagle-import") (part "TPSQPAD1-13"))
    )
    (comp (ref "TP6")
      (value "TPSQPAD1-13")
      (footprint "eagle-import:P1-13")
      (libsource (lib "eagle-import") (part "TPSQPAD1-13"))
    )
    (comp (ref "TP7")
      (value "TPSQPAD1-13")
      (footprint "eagle-import:P1-13")
      (libsource (lib "eagle-import") (part "TPSQPAD1-13"))
    )
    (comp (ref "TP8")
      (value "TPSQPAD1-13")
      (footprint "eagle-import:P1-13")
      (libsource (lib "eagle-import") (part "TPSQPAD1-13"))
    )
    (comp (ref "TP9")
      (value "TPSQPAD1-13")
      (footprint "eagle-import:P1-13")
      (libsource (lib "eagle-import") (part "TPSQPAD1-13"))
    )
    (comp (ref "TP10")
      (value "TPSQPAD1-13")
      (footprint "eagle-import:P1-13")
      (libsource (lib "eagle-import") (part "TPSQPAD1-13"))
    )
    (comp (ref "U$1")
      (value "TK90_EDGE")
      (footprint "eagle-import:TK-EDGE")
      (libsource (lib "eagle-import") (part "TK90_EDGE"))
    )
    (comp (ref "VIDEO(RF)")
      (value "RF")
      (footprint "eagle-import:P1-13")
      (libsource (lib "eagle-import") (part "TPPAD1-13"))
    )
    (comp (ref "X2")
      (value "POWER")
      (footprint "eagle-import:MONO")
      (libsource (lib "eagle-import") (part "JACK?-MONO"))
    )
    (comp (ref "XTAL")
      (value "14.3044MHz")
      (footprint "eagle-import:HC49_S")
      (libsource (lib "eagle-import") (part "CRYSTALHC49S"))
    )
  )
  (nets
    (net (code "1") (name "+5V") (class "Default")
      (node (ref "7805") (pin "OUT") (pinfunction "OUT_OUT") (pintype "passive"))
      (node (ref "C1") (pin "+") (pinfunction "+_+") (pintype "passive"))
      (node (ref "C12") (pin "2") (pinfunction "2_2") (pintype "passive"))
      (node (ref "C13") (pin "2") (pinfunction "2_2") (pintype "passive"))
      (node (ref "C14") (pin "2") (pinfunction "2_2") (pintype "passive"))
      (node (ref "C15") (pin "1") (pinfunction "1_1") (pintype "passive"))
      (node (ref "C16") (pin "1") (pinfunction "1_1") (pintype "passive"))
      (node (ref "C18") (pin "1") (pinfunction "1_1") (pintype "passive"))
      (node (ref "C19") (pin "1") (pinfunction "1_1") (pintype "passive"))
      (node (ref "C20") (pin "1") (pinfunction "1_1") (pintype "passive"))
      (node (ref "C21") (pin "1") (pinfunction "1_1") (pintype "passive"))
      (node (ref "C22") (pin "2") (pinfunction "2_2") (pintype "passive"))
      (node (ref "C24") (pin "2") (pinfunction "2_2") (pintype "passive"))
      (node (ref "C29") (pin "2") (pinfunction "2_2") (pintype "passive"))
      (node (ref "C31") (pin "2") (pinfunction "2_2") (pintype "passive"))
      (node (ref "C32") (pin "2") (pinfunction "2_2") (pintype "passive"))
      (node (ref "C33") (pin "2") (pinfunction "2_2") (pintype "passive"))
      (node (ref "D13") (pin "C") (pinfunction "K_C") (pintype "bidirectional"))
      (node (ref "D15") (pin "C") (pinfunction "K_C") (pintype "bidirectional"))
      (node (ref "D17") (pin "C") (pinfunction "K_C") (pintype "bidirectional"))
      (node (ref "IC1") (pin "11") (pinfunction "VCC_11") (pintype "power_in"))
      (node (ref "IC10") (pin "16") (pinfunction "VCC_16") (pintype "power_in"))
      (node (ref "IC11") (pin "20") (pinfunction "VCC_20") (pintype "power_in"))
      (node (ref "IC12") (pin "3") (pinfunction "CR_BIAS_3") (pintype "input"))
      (node (ref "IC13") (pin "9") (pinfunction "A7_9") (pintype "input"))
      (node (ref "IC14") (pin "9") (pinfunction "A7_9") (pintype "input"))
      (node (ref "IC15") (pin "9") (pinfunction "A7_9") (pintype "input"))
      (node (ref "IC16") (pin "9") (pinfunction "A7_9") (pintype "input"))
      (node (ref "IC17") (pin "9") (pinfunction "A7_9") (pintype "input"))
      (node (ref "IC18") (pin "9") (pinfunction "A7_9") (pintype "input"))
      (node (ref "IC19") (pin "9") (pinfunction "A7_9") (pintype "input"))
      (node (ref "IC2") (pin "1") (pinfunction "VPP_1") (pintype "input"))
      (node (ref "IC2") (pin "28") (pinfunction "VCC_28") (pintype "power_in"))
      (node (ref "IC20") (pin "9") (pinfunction "A7_9") (pintype "input"))
      (node (ref "IC21") (pin "9") (pinfunction "VCC_9") (pintype "power_in"))
      (node (ref "IC22") (pin "9") (pinfunction "VCC_9") (pintype "power_in"))
      (node (ref "IC23") (pin "9") (pinfunction "VCC_9") (pintype "power_in"))
      (node (ref "IC24") (pin "9") (pinfunction "VCC_9") (pintype "power_in"))
      (node (ref "IC25") (pin "14") (pinfunction "VCC_14") (pintype "power_in"))
      (node (ref "IC26") (pin "1") (pinfunction "I0_1") (pintype "input"))
      (node (ref "IC26") (pin "14") (pinfunction "VCC_14") (pintype "power_in"))
      (node (ref "IC27") (pin "14") (pinfunction "VCC_14") (pintype "power_in"))
      (node (ref "IC28") (pin "14") (pinfunction "VCC_14") (pintype "power_in"))
      (node (ref "IC3") (pin "40") (pinfunction "VCC_40") (pintype "power_in"))
      (node (ref "IC4") (pin "10") (pinfunction "PRE_10") (pintype "input"))
      (node (ref "IC4") (pin "13") (pinfunction "CLR_13") (pintype "input"))
      (node (ref "IC4") (pin "14") (pinfunction "VCC_14") (pintype "power_in"))
      (node (ref "IC5") (pin "1") (pinfunction "CLR_1") (pintype "input"))
      (node (ref "IC5") (pin "10") (pinfunction "PRE_10") (pintype "input"))
      (node (ref "IC5") (pin "13") (pinfunction "CLR_13") (pintype "input"))
      (node (ref "IC5") (pin "14") (pinfunction "VCC_14") (pintype "power_in"))
      (node (ref "IC5") (pin "4") (pinfunction "PRE_4") (pintype "input"))
      (node (ref "IC6") (pin "16") (pinfunction "VCC_16") (pintype "power_in"))
      (node (ref "IC7") (pin "16") (pinfunction "VCC_16") (pintype "power_in"))
      (node (ref "IC8") (pin "16") (pinfunction "VCC_16") (pintype "power_in"))
      (node (ref "IC9") (pin "16") (pinfunction "VCC_16") (pintype "power_in"))
      (node (ref "JP2") (pin "1") (pinfunction "1_1") (pintype "passive"))
      (node (ref "Q1") (pin "3") (pinfunction "C_3") (pintype "passive"))
      (node (ref "R17") (pin "2") (pinfunction "2_2") (pintype "passive"))
      (node (ref "R18") (pin "2") (pinfunction "2_2") (pintype "passive"))
      (node (ref "R19") (pin "2") (pinfunction "2_2") (pintype "passive"))
      (node (ref "R20") (pin "2") (pinfunction "2_2") (pintype "passive"))
      (node (ref "R21") (pin "2") (pinfunction "2_2") (pintype "passive"))
      (node (ref "R22") (pin "2") (pinfunction "2_2") (pintype "passive"))
      (node (ref "R23") (pin "2") (pinfunction "2_2") (pintype "passive"))
      (node (ref "R24") (pin "2") (pinfunction "2_2") (pintype "passive"))
      (node (ref "R29") (pin "2") (pinfunction "2_2") (pintype "passive"))
      (node (ref "R30") (pin "1") (pinfunction "1_1") (pintype "passive"))
      (node (ref "R31") (pin "1") (pinfunction "1_1") (pintype "passive"))
      (node (ref "R32") (pin "1") (pinfunction "1_1") (pintype "passive"))
      (node (ref "R35") (pin "1") (pinfunction "1_1") (pintype "passive"))
      (node (ref "R36") (pin "1") (pinfunction "1_1") (pintype "passive"))
      (node (ref "R37") (pin "1") (pinfunction "1_1") (pintype "passive"))
      (node (ref "R38") (pin "1") (pinfunction "1_1") (pintype "passive"))
      (node (ref "R39") (pin "1") (pinfunction "1_1") (pintype "passive"))
      (node (ref "R40") (pin "2") (pinfunction "2_2") (pintype "passive"))
      (node (ref "R43") (pin "2") (pinfunction "2_2") (pintype "passive"))
      (node (ref "R48") (pin "2") (pinfunction "2_2") (pintype "passive"))
      (node (ref "R51") (pin "2") (pinfunction "2_2") (pintype "passive"))
      (node (ref "R74_") (pin "2") (pinfunction "2_2") (pintype "passive"))
      (node (ref "U$1") (pin "3A") (pinfunction "EDGE_3A") (pintype "bidirectional"))
    )
    (net (code "2") (name "+12V") (class "Default")
      (node (ref "C43") (pin "2") (pinfunction "2_2") (pintype "passive"))
      (node (ref "C53") (pin "+") (pinfunction "+_+") (pintype "passive"))
      (node (ref "D24") (pin "C") (pinfunction "K_C") (pintype "bidirectional"))
      (node (ref "IC11") (pin "5") (pinfunction "+12V_5") (pintype "power_in"))
      (node (ref "IC12") (pin "14") (pinfunction "RFVCC_14") (pintype "power_in"))
      (node (ref "IC12") (pin "16") (pinfunction "CRVCC_16") (pintype "power_in"))
      (node (ref "L1") (pin "2") (pinfunction "A_2") (pintype "passive"))
      (node (ref "R54") (pin "1") (pinfunction "1_1") (pintype "passive"))
      (node (ref "R57") (pin "1") (pinfunction "1_1") (pintype "passive"))
      (node (ref "R58") (pin "1") (pinfunction "1_1") (pintype "passive"))
      (node (ref "R59") (pin "1") (pinfunction "1_1") (pintype "passive"))
      (node (ref "R68") (pin "1") (pinfunction "1_1") (pintype "passive"))
      (node (ref "U$1") (pin "22B") (pinfunction "EDGE_22B") (pintype "bidirectional"))
    )
    (net (code "3") (name "-5V") (class "Default")
      (node (ref "C50") (pin "1") (pinfunction "1_1") (pintype "passive"))
      (node (ref "D21") (pin "A") (pinfunction "A_A") (pintype "bidirectional"))
      (node (ref "J3") (pin "1") (pinfunction "1_1") (pintype "passive"))
      (node (ref "R67") (pin "1") (pinfunction "1_1") (pintype "passive"))
      (node (ref "U$1") (pin "20B") (pinfunction "EDGE_20B") (pintype "bidirectional"))
    )
    (net (code "4") (name "/+12V_UNREG") (class "Default")
      (node (ref "C48") (pin "1") (pinfunction "1_1") (pintype "passive"))
      (node (ref "C51") (pin "1") (pinfunction "1_1") (pintype "passive"))
      (node (ref "Q5") (pin "E") (pinfunction "E_E") (pintype "passive"))
      (node (ref "Q6") (pin "E") (pinfunction "E_E") (pintype "passive"))
      (node (ref "U$1") (pin "23B") (pinfunction "EDGE_23B") (pintype "bidirectional"))
    )
    (net (code "5") (name "/A0") (class "Default")
      (node (ref "IC1") (pin "30") (pinfunction "A0_30") (pintype "output"))
      (node (ref "IC2") (pin "10") (pinfunction "A0_10") (pintype "input"))
      (node (ref "IC7") (pin "3") (pinfunction "1B_3") (pintype "input"))
      (node (ref "IC8") (pin "3") (pinfunction "1B_3") (pintype "input"))
      (node (ref "Q1") (pin "2") (pinfunction "B_2") (pintype "passive"))
      (node (ref "U$1") (pin "9A") (pinfunction "EDGE_9A") (pintype "bidirectional"))
    )
    (net (code "6") (name "/A1") (class "Default")
      (node (ref "IC1") (pin "31") (pinfunction "A1_31") (pintype "output"))
      (node (ref "IC2") (pin "9") (pinfunction "A1_9") (pintype "input"))
      (node (ref "IC7") (pin "6") (pinfunction "2B_6") (pintype "input"))
      (node (ref "IC8") (pin "6") (pinfunction "2B_6") (pintype "input"))
      (node (ref "U$1") (pin "10A") (pinfunction "EDGE_10A") (pintype "bidirectional"))
    )
    (net (code "7") (name "/A2") (class "Default")
      (node (ref "IC1") (pin "32") (pinfunction "A2_32") (pintype "output"))
      (node (ref "IC2") (pin "8") (pinfunction "A2_8") (pintype "input"))
      (node (ref "IC7") (pin "13") (pinfunction "4B_13") (pintype "input"))
      (node (ref "IC8") (pin "13") (pinfunction "4B_13") (pintype "input"))
      (node (ref "U$1") (pin "11A") (pinfunction "EDGE_11A") (pintype "bidirectional"))
    )
    (net (code "8") (name "/A3") (class "Default")
      (node (ref "IC1") (pin "33") (pinfunction "A3_33") (pintype "output"))
      (node (ref "IC2") (pin "7") (pinfunction "A3_7") (pintype "input"))
      (node (ref "IC7") (pin "10") (pinfunction "3B_10") (pintype "input"))
      (node (ref "IC8") (pin "10") (pinfunction "3B_10") (pintype "input"))
      (node (ref "U$1") (pin "12A") (pinfunction "EDGE_12A") (pintype "bidirectional"))
    )
    (net (code "9") (name "/A4") (class "Default")
      (node (ref "IC1") (pin "34") (pinfunction "A4_34") (pintype "output"))
      (node (ref "IC2") (pin "6") (pinfunction "A4_6") (pintype "input"))
      (node (ref "IC6") (pin "6") (pinfunction "2B_6") (pintype "input"))
      (node (ref "IC9") (pin "6") (pinfunction "2B_6") (pintype "input"))
      (node (ref "U$1") (pin "24A") (pinfunction "EDGE_24A") (pintype "bidirectional"))
    )
    (net (code "10") (name "/A5") (class "Default")
      (node (ref "IC1") (pin "35") (pinfunction "A5_35") (pintype "output"))
      (node (ref "IC2") (pin "5") (pinfunction "A5_5") (pintype "input"))
      (node (ref "IC6") (pin "13") (pinfunction "4B_13") (pintype "input"))
      (node (ref "IC9") (pin "13") (pinfunction "4B_13") (pintype "input"))
      (node (ref "U$1") (pin "23A") (pinfunction "EDGE_23A") (pintype "bidirectional"))
    )
    (net (code "11") (name "/A6") (class "Default")
      (node (ref "IC1") (pin "36") (pinfunction "A6_36") (pintype "output"))
      (node (ref "IC2") (pin "4") (pinfunction "A6_4") (pintype "input"))
      (node (ref "IC21") (pin "14") (pinfunction "A0_14") (pintype "input"))
      (node (ref "IC22") (pin "14") (pinfunction "A0_14") (pintype "input"))
      (node (ref "IC23") (pin "14") (pinfunction "A0_14") (pintype "input"))
      (node (ref "IC24") (pin "14") (pinfunction "A0_14") (pintype "input"))
      (node (ref "IC5") (pin "12") (pinfunction "D_12") (pintype "input"))
      (node (ref "IC9") (pin "10") (pinfunction "3B_10") (pintype "input"))
      (node (ref "U$1") (pin "22A") (pinfunction "EDGE_22A") (pintype "bidirectional"))
    )
    (net (code "12") (name "/A7") (class "Default")
      (node (ref "IC1") (pin "37") (pinfunction "A7_37") (pintype "output"))
      (node (ref "IC2") (pin "3") (pinfunction "A7_3") (pintype "input"))
      (node (ref "IC26") (pin "12") (pinfunction "I0_12") (pintype "input"))
      (node (ref "IC8") (pin "2") (pinfunction "1A_2") (pintype "input"))
      (node (ref "U$1") (pin "21A") (pinfunction "EDGE_21A") (pintype "bidirectional"))
    )
    (net (code "13") (name "/A7'") (class "Default")
      (node (ref "IC21") (pin "10") (pinfunction "A7_10") (pintype "input"))
      (node (ref "IC22") (pin "10") (pinfunction "A7_10") (pintype "input"))
      (node (ref "IC23") (pin "10") (pinfunction "A7_10") (pintype "input"))
      (node (ref "IC24") (pin "10") (pinfunction "A7_10") (pintype "input"))
      (node (ref "IC26") (pin "8") (pinfunction "O_8") (pintype "output"))
    )
    (net (code "14") (name "/A8") (class "Default")
      (node (ref "D2") (pin "C") (pinfunction "K_C") (pintype "bidirectional"))
      (node (ref "IC1") (pin "38") (pinfunction "A8_38") (pintype "output"))
      (node (ref "IC2") (pin "25") (pinfunction "A8_25") (pintype "input"))
      (node (ref "IC7") (pin "5") (pinfunction "2A_5") (pintype "input"))
      (node (ref "IC8") (pin "5") (pinfunction "2A_5") (pintype "input"))
      (node (ref "U$1") (pin "26B") (pinfunction "EDGE_26B") (pintype "bidirectional"))
    )
    (net (code "15") (name "/A8-1") (class "Default")
      (node (ref "IC21") (pin "7") (pinfunction "A5_7") (pintype "input"))
      (node (ref "IC22") (pin "7") (pinfunction "A5_7") (pintype "input"))
      (node (ref "IC23") (pin "7") (pinfunction "A5_7") (pintype "input"))
      (node (ref "IC24") (pin "7") (pinfunction "A5_7") (pintype "input"))
      (node (ref "IC7") (pin "7") (pinfunction "2Y_7") (pintype "output"))
    )
    (net (code "16") (name "/A9") (class "Default")
      (node (ref "D3") (pin "C") (pinfunction "K_C") (pintype "bidirectional"))
      (node (ref "IC1") (pin "39") (pinfunction "A9_39") (pintype "output"))
      (node (ref "IC2") (pin "24") (pinfunction "A9_24") (pintype "input"))
      (node (ref "IC7") (pin "14") (pinfunction "4A_14") (pintype "input"))
      (node (ref "IC8") (pin "14") (pinfunction "4A_14") (pintype "input"))
      (node (ref "U$1") (pin "27A") (pinfunction "EDGE_27A") (pintype "bidirectional"))
    )
    (net (code "17") (name "/A9-2") (class "Default")
      (node (ref "IC21") (pin "8") (pinfunction "A4_8") (pintype "input"))
      (node (ref "IC22") (pin "8") (pinfunction "A4_8") (pintype "input"))
      (node (ref "IC23") (pin "8") (pinfunction "A4_8") (pintype "input"))
      (node (ref "IC24") (pin "8") (pinfunction "A4_8") (pintype "input"))
      (node (ref "IC7") (pin "12") (pinfunction "4Y_12") (pintype "output"))
    )
    (net (code "18") (name "/A10") (class "Default")
      (node (ref "D4") (pin "C") (pinfunction "K_C") (pintype "bidirectional"))
      (node (ref "IC1") (pin "40") (pinfunction "A10_40") (pintype "output"))
      (node (ref "IC2") (pin "21") (pinfunction "A10_21") (pintype "input"))
      (node (ref "IC7") (pin "11") (pinfunction "3A_11") (pintype "input"))
      (node (ref "IC8") (pin "11") (pinfunction "3A_11") (pintype "input"))
      (node (ref "U$1") (pin "27B") (pinfunction "EDGE_27B") (pintype "bidirectional"))
    )
    (net (code "19") (name "/A10-3") (class "Default")
      (node (ref "IC21") (pin "11") (pinfunction "A3_11") (pintype "input"))
      (node (ref "IC22") (pin "11") (pinfunction "A3_11") (pintype "input"))
      (node (ref "IC23") (pin "11") (pinfunction "A3_11") (pintype "input"))
      (node (ref "IC24") (pin "11") (pinfunction "A3_11") (pintype "input"))
      (node (ref "IC7") (pin "9") (pinfunction "3Y_9") (pintype "output"))
    )
    (net (code "20") (name "/A11") (class "Default")
      (node (ref "D5") (pin "C") (pinfunction "K_C") (pintype "bidirectional"))
      (node (ref "IC1") (pin "1") (pinfunction "A11_1") (pintype "output"))
      (node (ref "IC2") (pin "23") (pinfunction "A11_23") (pintype "input"))
      (node (ref "IC6") (pin "5") (pinfunction "2A_5") (pintype "input"))
      (node (ref "IC9") (pin "5") (pinfunction "2A_5") (pintype "input"))
      (node (ref "U$1") (pin "28A") (pinfunction "EDGE_28A") (pintype "bidirectional"))
    )
    (net (code "21") (name "/A11-4") (class "Default")
      (node (ref "IC21") (pin "12") (pinfunction "A2_12") (pintype "input"))
      (node (ref "IC22") (pin "12") (pinfunction "A2_12") (pintype "input"))
      (node (ref "IC23") (pin "12") (pinfunction "A2_12") (pintype "input"))
      (node (ref "IC24") (pin "12") (pinfunction "A2_12") (pintype "input"))
      (node (ref "IC6") (pin "7") (pinfunction "2Y_7") (pintype "output"))
    )
    (net (code "22") (name "/A12") (class "Default")
      (node (ref "D6") (pin "C") (pinfunction "K_C") (pintype "bidirectional"))
      (node (ref "IC1") (pin "2") (pinfunction "A12_2") (pintype "output"))
      (node (ref "IC2") (pin "2") (pinfunction "A12_2") (pintype "input"))
      (node (ref "IC6") (pin "14") (pinfunction "4A_14") (pintype "input"))
      (node (ref "IC9") (pin "14") (pinfunction "4A_14") (pintype "input"))
      (node (ref "U$1") (pin "2A") (pinfunction "EDGE_2A") (pintype "bidirectional"))
    )
    (net (code "23") (name "/A12-5") (class "Default")
      (node (ref "IC21") (pin "13") (pinfunction "A1_13") (pintype "input"))
      (node (ref "IC22") (pin "13") (pinfunction "A1_13") (pintype "input"))
      (node (ref "IC23") (pin "13") (pinfunction "A1_13") (pintype "input"))
      (node (ref "IC24") (pin "13") (pinfunction "A1_13") (pintype "input"))
      (node (ref "IC6") (pin "12") (pinfunction "4Y_12") (pintype "output"))
    )
    (net (code "24") (name "/A13") (class "Default")
      (node (ref "D7") (pin "C") (pinfunction "K_C") (pintype "bidirectional"))
      (node (ref "IC1") (pin "3") (pinfunction "A13_3") (pintype "output"))
      (node (ref "IC2") (pin "26") (pinfunction "A13_26") (pintype "input"))
      (node (ref "IC7") (pin "2") (pinfunction "1A_2") (pintype "input"))
      (node (ref "IC9") (pin "11") (pinfunction "3A_11") (pintype "input"))
      (node (ref "U$1") (pin "2B") (pinfunction "EDGE_2B") (pintype "bidirectional"))
    )
    (net (code "25") (name "/A13-0") (class "Default")
      (node (ref "IC21") (pin "6") (pinfunction "A6_6") (pintype "input"))
      (node (ref "IC22") (pin "6") (pinfunction "A6_6") (pintype "input"))
      (node (ref "IC23") (pin "6") (pinfunction "A6_6") (pintype "input"))
      (node (ref "IC24") (pin "6") (pinfunction "A6_6") (pintype "input"))
      (node (ref "IC7") (pin "4") (pinfunction "1Y_4") (pintype "output"))
    )
    (net (code "26") (name "/A14") (class "Default")
      (node (ref "D12") (pin "A") (pinfunction "A_A") (pintype "bidirectional"))
      (node (ref "D8") (pin "C") (pinfunction "K_C") (pintype "bidirectional"))
      (node (ref "IC1") (pin "4") (pinfunction "A14_4") (pintype "output"))
      (node (ref "IC25") (pin "4") (pinfunction "I0_4") (pintype "input"))
      (node (ref "IC27") (pin "12") (pinfunction "I0_12") (pintype "input"))
      (node (ref "IC28") (pin "1") (pinfunction "I_1") (pintype "input"))
      (node (ref "IC3") (pin "37") (pinfunction "A14_37") (pintype "input"))
      (node (ref "U$1") (pin "1A") (pinfunction "EDGE_1A") (pintype "bidirectional"))
    )
    (net (code "27") (name "/A15") (class "Default")
      (node (ref "D11") (pin "A") (pinfunction "A_A") (pintype "bidirectional"))
      (node (ref "D9") (pin "C") (pinfunction "K_C") (pintype "bidirectional"))
      (node (ref "IC1") (pin "5") (pinfunction "A15_5") (pintype "output"))
      (node (ref "IC25") (pin "13") (pinfunction "I1_13") (pintype "input"))
      (node (ref "IC27") (pin "13") (pinfunction "I1_13") (pintype "input"))
      (node (ref "IC3") (pin "38") (pinfunction "A15_38") (pintype "input"))
      (node (ref "U$1") (pin "1B") (pinfunction "EDGE_1B") (pintype "bidirectional"))
    )
    (net (code "28") (name "/AA0") (class "Default")
      (node (ref "IC13") (pin "5") (pinfunction "A0_5") (pintype "input"))
      (node (ref "IC14") (pin "5") (pinfunction "A0_5") (pintype "input"))
      (node (ref "IC15") (pin "5") (pinfunction "A0_5") (pintype "input"))
      (node (ref "IC16") (pin "5") (pinfunction "A0_5") (pintype "input"))
      (node (ref "IC17") (pin "5") (pinfunction "A0_5") (pintype "input"))
      (node (ref "IC18") (pin "5") (pinfunction "A0_5") (pintype "input"))
      (node (ref "IC19") (pin "5") (pinfunction "A0_5") (pintype "input"))
      (node (ref "IC20") (pin "5") (pinfunction "A0_5") (pintype "input"))
      (node (ref "IC3") (pin "9") (pinfunction "A0_9") (pintype "output"))
      (node (ref "R9") (pin "1") (pinfunction "1_1") (pintype "passive"))
    )
    (net (code "29") (name "/AA1") (class "Default")
      (node (ref "IC13") (pin "7") (pinfunction "A1_7") (pintype "input"))
      (node (ref "IC14") (pin "7") (pinfunction "A1_7") (pintype "input"))
      (node (ref "IC15") (pin "7") (pinfunction "A1_7") (pintype "input"))
      (node (ref "IC16") (pin "7") (pinfunction "A1_7") (pintype "input"))
      (node (ref "IC17") (pin "7") (pinfunction "A1_7") (pintype "input"))
      (node (ref "IC18") (pin "7") (pinfunction "A1_7") (pintype "input"))
      (node (ref "IC19") (pin "7") (pinfunction "A1_7") (pintype "input"))
      (node (ref "IC20") (pin "7") (pinfunction "A1_7") (pintype "input"))
      (node (ref "IC3") (pin "7") (pinfunction "A1_7") (pintype "output"))
      (node (ref "R11") (pin "1") (pinfunction "1_1") (pintype "passive"))
    )
    (net (code "30") (name "/AA2") (class "Default")
      (node (ref "IC13") (pin "6") (pinfunction "A2_6") (pintype "input"))
      (node (ref "IC14") (pin "6") (pinfunction "A2_6") (pintype "input"))
      (node (ref "IC15") (pin "6") (pinfunction "A2_6") (pintype "input"))
      (node (ref "IC16") (pin "6") (pinfunction "A2_6") (pintype "input"))
      (node (ref "IC17") (pin "6") (pinfunction "A2_6") (pintype "input"))
      (node (ref "IC18") (pin "6") (pinfunction "A2_6") (pintype "input"))
      (node (ref "IC19") (pin "6") (pinfunction "A2_6") (pintype "input"))
      (node (ref "IC20") (pin "6") (pinfunction "A2_6") (pintype "input"))
      (node (ref "IC3") (pin "8") (pinfunction "A2_8") (pintype "output"))
      (node (ref "R10") (pin "1") (pinfunction "1_1") (pintype "passive"))
    )
    (net (code "31") (name "/AA3") (class "Default")
      (node (ref "IC13") (pin "12") (pinfunction "A3_12") (pintype "input"))
      (node (ref "IC14") (pin "12") (pinfunction "A3_12") (pintype "input"))
      (node (ref "IC15") (pin "12") (pinfunction "A3_12") (pintype "input"))
      (node (ref "IC16") (pin "12") (pinfunction "A3_12") (pintype "input"))
      (node (ref "IC17") (pin "12") (pinfunction "A3_12") (pintype "input"))
      (node (ref "IC18") (pin "12") (pinfunction "A3_12") (pintype "input"))
      (node (ref "IC19") (pin "12") (pinfunction "A3_12") (pintype "input"))
      (node (ref "IC20") (pin "12") (pinfunction "A3_12") (pintype "input"))
      (node (ref "IC3") (pin "4") (pinfunction "A3_4") (pintype "output"))
      (node (ref "R14") (pin "1") (pinfunction "1_1") (pintype "passive"))
    )
    (net (code "32") (name "/AA4") (class "Default")
      (node (ref "IC13") (pin "11") (pinfunction "A4_11") (pintype "input"))
      (node (ref "IC14") (pin "11") (pinfunction "A4_11") (pintype "input"))
      (node (ref "IC15") (pin "11") (pinfunction "A4_11") (pintype "input"))
      (node (ref "IC16") (pin "11") (pinfunction "A4_11") (pintype "input"))
      (node (ref "IC17") (pin "11") (pinfunction "A4_11") (pintype "input"))
      (node (ref "IC18") (pin "11") (pinfunction "A4_11") (pintype "input"))
      (node (ref "IC19") (pin "11") (pinfunction "A4_11") (pintype "input"))
      (node (ref "IC20") (pin "11") (pinfunction "A4_11") (pintype "input"))
      (node (ref "IC3") (pin "5") (pinfunction "A4_5") (pintype "output"))
      (node (ref "R13") (pin "1") (pinfunction "1_1") (pintype "passive"))
    )
    (net (code "33") (name "/AA5") (class "Default")
      (node (ref "IC13") (pin "10") (pinfunction "A5_10") (pintype "input"))
      (node (ref "IC14") (pin "10") (pinfunction "A5_10") (pintype "input"))
      (node (ref "IC15") (pin "10") (pinfunction "A5_10") (pintype "input"))
      (node (ref "IC16") (pin "10") (pinfunction "A5_10") (pintype "input"))
      (node (ref "IC17") (pin "10") (pinfunction "A5_10") (pintype "input"))
      (node (ref "IC18") (pin "10") (pinfunction "A5_10") (pintype "input"))
      (node (ref "IC19") (pin "10") (pinfunction "A5_10") (pintype "input"))
      (node (ref "IC20") (pin "10") (pinfunction "A5_10") (pintype "input"))
      (node (ref "IC3") (pin "6") (pinfunction "A5_6") (pintype "output"))
      (node (ref "R12") (pin "1") (pinfunction "1_1") (pintype "passive"))
    )
    (net (code "34") (name "/AA6") (class "Default")
      (node (ref "IC13") (pin "13") (pinfunction "A6_13") (pintype "input"))
      (node (ref "IC14") (pin "13") (pinfunction "A6_13") (pintype "input"))
      (node (ref "IC15") (pin "13") (pinfunction "A6_13") (pintype "input"))
      (node (ref "IC16") (pin "13") (pinfunction "A6_13") (pintype "input"))
      (node (ref "IC17") (pin "13") (pinfunction "A6_13") (pintype "input"))
      (node (ref "IC18") (pin "13") (pinfunction "A6_13") (pintype "input"))
      (node (ref "IC19") (pin "13") (pinfunction "A6_13") (pintype "input"))
      (node (ref "IC20") (pin "13") (pinfunction "A6_13") (pintype "input"))
      (node (ref "IC3") (pin "3") (pinfunction "A6_3") (pintype "output"))
      (node (ref "R15") (pin "1") (pinfunction "1_1") (pintype "passive"))
    )
    (net (code "35") (name "/CARRIER") (class "Default")
      (node (ref "C47") (pin "1") (pinfunction "1_1") (pintype "passive"))
      (node (ref "D17") (pin "A") (pinfunction "A_A") (pintype "bidirectional"))
      (node (ref "D18") (pin "C") (pinfunction "K_C") (pintype "bidirectional"))
      (node (ref "IC3") (pin "39") (pinfunction "CARRIER_39") (pintype "output"))
      (node (ref "R64") (pin "2") (pinfunction "2_2") (pintype "passive"))
      (node (ref "R71") (pin "2") (pinfunction "2_2") (pintype "passive"))
    )
    (net (code "36") (name "/CLK") (class "Default")
      (node (ref "C9") (pin "2") (pinfunction "2_2") (pintype "passive"))
      (node (ref "IC3") (pin "36") (pinfunction "CKOUT_36") (pintype "output"))
      (node (ref "R49") (pin "2") (pinfunction "2_2") (pintype "passive"))
      (node (ref "R51") (pin "1") (pinfunction "1_1") (pintype "passive"))
      (node (ref "U$1") (pin "8A") (pinfunction "EDGE_8A") (pintype "bidirectional"))
    )
    (net (code "37") (name "/D0") (class "Default")
      (node (ref "IC1") (pin "14") (pinfunction "D0_14") (pintype "bidirectional"))
      (node (ref "IC10") (pin "3") (pinfunction "Y1_3") (pintype "tri_state"))
      (node (ref "IC2") (pin "11") (pinfunction "O0_11") (pintype "tri_state"))
      (node (ref "IC21") (pin "2") (pinfunction "I/O1_2") (pintype "bidirectional"))
      (node (ref "IC23") (pin "2") (pinfunction "I/O1_2") (pintype "bidirectional"))
      (node (ref "R1") (pin "2") (pinfunction "2_2") (pintype "passive"))
      (node (ref "R17") (pin "1") (pinfunction "1_1") (pintype "passive"))
      (node (ref "U$1") (pin "6B") (pinfunction "EDGE_6B") (pintype "bidirectional"))
    )
    (net (code "38") (name "/D0'") (class "Default")
      (node (ref "IC20") (pin "14") (pinfunction "DO_14") (pintype "bidirectional"))
      (node (ref "IC20") (pin "2") (pinfunction "DI_2") (pintype "bidirectional"))
      (node (ref "IC3") (pin "25") (pinfunction "D0_25") (pintype "bidirectional"))
      (node (ref "R1") (pin "1") (pinfunction "1_1") (pintype "passive"))
    )
    (net (code "39") (name "/D1") (class "Default")
      (node (ref "IC1") (pin "15") (pinfunction "D1_15") (pintype "bidirectional"))
      (node (ref "IC10") (pin "5") (pinfunction "Y2_5") (pintype "tri_state"))
      (node (ref "IC2") (pin "12") (pinfunction "O1_12") (pintype "tri_state"))
      (node (ref "IC21") (pin "3") (pinfunction "I/O2_3") (pintype "bidirectional"))
      (node (ref "IC23") (pin "3") (pinfunction "I/O2_3") (pintype "bidirectional"))
      (node (ref "R18") (pin "1") (pinfunction "1_1") (pintype "passive"))
      (node (ref "R2") (pin "2") (pinfunction "2_2") (pintype "passive"))
      (node (ref "U$1") (pin "7B") (pinfunction "EDGE_7B") (pintype "bidirectional"))
    )
    (net (code "40") (name "/D1'") (class "Default")
      (node (ref "IC19") (pin "14") (pinfunction "DO_14") (pintype "bidirectional"))
      (node (ref "IC19") (pin "2") (pinfunction "DI_2") (pintype "bidirectional"))
      (node (ref "IC3") (pin "26") (pinfunction "D1_26") (pintype "bidirectional"))
      (node (ref "R2") (pin "1") (pinfunction "1_1") (pintype "passive"))
    )
    (net (code "41") (name "/D2") (class "Default")
      (node (ref "IC1") (pin "12") (pinfunction "D2_12") (pintype "bidirectional"))
      (node (ref "IC10") (pin "7") (pinfunction "Y3_7") (pintype "tri_state"))
      (node (ref "IC2") (pin "13") (pinfunction "O2_13") (pintype "tri_state"))
      (node (ref "IC21") (pin "15") (pinfunction "I/O3_15") (pintype "bidirectional"))
      (node (ref "IC23") (pin "15") (pinfunction "I/O3_15") (pintype "bidirectional"))
      (node (ref "R19") (pin "1") (pinfunction "1_1") (pintype "passive"))
      (node (ref "R3") (pin "2") (pinfunction "2_2") (pintype "passive"))
      (node (ref "U$1") (pin "8B") (pinfunction "EDGE_8B") (pintype "bidirectional"))
    )
    (net (code "42") (name "/D2'") (class "Default")
      (node (ref "IC18") (pin "14") (pinfunction "DO_14") (pintype "bidirectional"))
      (node (ref "IC18") (pin "2") (pinfunction "DI_2") (pintype "bidirectional"))
      (node (ref "IC3") (pin "27") (pinfunction "D2_27") (pintype "bidirectional"))
      (node (ref "R3") (pin "1") (pinfunction "1_1") (pintype "passive"))
    )
    (net (code "43") (name "/D3") (class "Default")
      (node (ref "IC1") (pin "8") (pinfunction "D3_8") (pintype "bidirectional"))
      (node (ref "IC10") (pin "9") (pinfunction "Y4_9") (pintype "tri_state"))
      (node (ref "IC2") (pin "15") (pinfunction "O3_15") (pintype "tri_state"))
      (node (ref "IC21") (pin "17") (pinfunction "I/O4_17") (pintype "bidirectional"))
      (node (ref "IC23") (pin "17") (pinfunction "I/O4_17") (pintype "bidirectional"))
      (node (ref "R20") (pin "1") (pinfunction "1_1") (pintype "passive"))
      (node (ref "R4") (pin "2") (pinfunction "2_2") (pintype "passive"))
      (node (ref "U$1") (pin "11B") (pinfunction "EDGE_11B") (pintype "bidirectional"))
    )
    (net (code "44") (name "/D3'") (class "Default")
      (node (ref "IC17") (pin "14") (pinfunction "DO_14") (pintype "bidirectional"))
      (node (ref "IC17") (pin "2") (pinfunction "DI_2") (pintype "bidirectional"))
      (node (ref "IC3") (pin "28") (pinfunction "D3_28") (pintype "bidirectional"))
      (node (ref "R4") (pin "1") (pinfunction "1_1") (pintype "passive"))
    )
    (net (code "45") (name "/D4") (class "Default")
      (node (ref "IC1") (pin "7") (pinfunction "D4_7") (pintype "bidirectional"))
      (node (ref "IC10") (pin "11") (pinfunction "Y5_11") (pintype "tri_state"))
      (node (ref "IC2") (pin "16") (pinfunction "O4_16") (pintype "tri_state"))
      (node (ref "IC22") (pin "2") (pinfunction "I/O1_2") (pintype "bidirectional"))
      (node (ref "IC24") (pin "2") (pinfunction "I/O1_2") (pintype "bidirectional"))
      (node (ref "R21") (pin "1") (pinfunction "1_1") (pintype "passive"))
      (node (ref "R5") (pin "2") (pinfunction "2_2") (pintype "passive"))
      (node (ref "U$1") (pin "12B") (pinfunction "EDGE_12B") (pintype "bidirectional"))
    )
    (net (code "46") (name "/D4'") (class "Default")
      (node (ref "IC16") (pin "14") (pinfunction "DO_14") (pintype "bidirectional"))
      (node (ref "IC16") (pin "2") (pinfunction "DI_2") (pintype "bidirectional"))
      (node (ref "IC3") (pin "29") (pinfunction "D4_29") (pintype "bidirectional"))
      (node (ref "R5") (pin "1") (pinfunction "1_1") (pintype "passive"))
    )
    (net (code "47") (name "/D5") (class "Default")
      (node (ref "IC1") (pin "9") (pinfunction "D5_9") (pintype "bidirectional"))
      (node (ref "IC2") (pin "17") (pinfunction "O5_17") (pintype "tri_state"))
      (node (ref "IC22") (pin "3") (pinfunction "I/O2_3") (pintype "bidirectional"))
      (node (ref "IC24") (pin "3") (pinfunction "I/O2_3") (pintype "bidirectional"))
      (node (ref "R22") (pin "1") (pinfunction "1_1") (pintype "passive"))
      (node (ref "R6") (pin "2") (pinfunction "2_2") (pintype "passive"))
      (node (ref "U$1") (pin "10B") (pinfunction "EDGE_10B") (pintype "bidirectional"))
    )
    (net (code "48") (name "/D5'") (class "Default")
      (node (ref "IC15") (pin "14") (pinfunction "DO_14") (pintype "bidirectional"))
      (node (ref "IC15") (pin "2") (pinfunction "DI_2") (pintype "bidirectional"))
      (node (ref "IC3") (pin "30") (pinfunction "D5_30") (pintype "bidirectional"))
      (node (ref "R6") (pin "1") (pinfunction "1_1") (pintype "passive"))
    )
    (net (code "49") (name "/D6") (class "Default")
      (node (ref "IC1") (pin "10") (pinfunction "D6_10") (pintype "bidirectional"))
      (node (ref "IC10") (pin "13") (pinfunction "Y6_13") (pintype "tri_state"))
      (node (ref "IC2") (pin "18") (pinfunction "O6_18") (pintype "tri_state"))
      (node (ref "IC22") (pin "15") (pinfunction "I/O3_15") (pintype "bidirectional"))
      (node (ref "IC24") (pin "15") (pinfunction "I/O3_15") (pintype "bidirectional"))
      (node (ref "R23") (pin "1") (pinfunction "1_1") (pintype "passive"))
      (node (ref "R7") (pin "2") (pinfunction "2_2") (pintype "passive"))
      (node (ref "U$1") (pin "9B") (pinfunction "EDGE_9B") (pintype "bidirectional"))
    )
    (net (code "50") (name "/D6'") (class "Default")
      (node (ref "IC14") (pin "14") (pinfunction "DO_14") (pintype "bidirectional"))
      (node (ref "IC14") (pin "2") (pinfunction "DI_2") (pintype "bidirectional"))
      (node (ref "IC3") (pin "31") (pinfunction "D6_31") (pintype "bidirectional"))
      (node (ref "R7") (pin "1") (pinfunction "1_1") (pintype "passive"))
    )
    (net (code "51") (name "/D7") (class "Default")
      (node (ref "D1") (pin "A") (pinfunction "A_A") (pintype "bidirectional"))
      (node (ref "IC1") (pin "13") (pinfunction "D7_13") (pintype "bidirectional"))
      (node (ref "IC2") (pin "19") (pinfunction "O7_19") (pintype "tri_state"))
      (node (ref "IC22") (pin "17") (pinfunction "I/O4_17") (pintype "bidirectional"))
      (node (ref "IC24") (pin "17") (pinfunction "I/O4_17") (pintype "bidirectional"))
      (node (ref "R24") (pin "1") (pinfunction "1_1") (pintype "passive"))
      (node (ref "R8") (pin "2") (pinfunction "2_2") (pintype "passive"))
      (node (ref "U$1") (pin "3B") (pinfunction "EDGE_3B") (pintype "bidirectional"))
    )
    (net (code "52") (name "/D7'") (class "Default")
      (node (ref "IC13") (pin "14") (pinfunction "DO_14") (pintype "bidirectional"))
      (node (ref "IC13") (pin "2") (pinfunction "DI_2") (pintype "bidirectional"))
      (node (ref "IC3") (pin "32") (pinfunction "D7_32") (pintype "bidirectional"))
      (node (ref "R8") (pin "1") (pinfunction "1_1") (pintype "passive"))
    )
    (net (code "53") (name "/MREQ'") (class "Default")
      (node (ref "D10") (pin "C") (pinfunction "K_C") (pintype "bidirectional"))
      (node (ref "IC3") (pin "15") (pinfunction "~{MREQ}_15") (pintype "input"))
      (node (ref "R34") (pin "2") (pinfunction "2_2") (pintype "passive"))
    )
    (net (code "54") (name "/N$33") (class "Default")
      (node (ref "C26") (pin "1") (pinfunction "1_1") (pintype "passive"))
      (node (ref "C27") (pin "1") (pinfunction "1_1") (pintype "passive"))
      (node (ref "IC13") (pin "1") (pinfunction "VBB_1") (pintype "input"))
      (node (ref "IC14") (pin "1") (pinfunction "VBB_1") (pintype "input"))
      (node (ref "IC15") (pin "1") (pinfunction "VBB_1") (pintype "input"))
      (node (ref "IC16") (pin "1") (pinfunction "VBB_1") (pintype "input"))
      (node (ref "IC17") (pin "1") (pinfunction "VBB_1") (pintype "input"))
      (node (ref "IC18") (pin "1") (pinfunction "VBB_1") (pintype "input"))
      (node (ref "IC19") (pin "1") (pinfunction "VBB_1") (pintype "input"))
      (node (ref "IC20") (pin "1") (pinfunction "VBB_1") (pintype "input"))
      (node (ref "J3") (pin "2") (pinfunction "2_2") (pintype "passive"))
    )
    (net (code "55") (name "/RESET") (class "Default")
      (node (ref "D10") (pin "A") (pinfunction "A_A") (pintype "bidirectional"))
      (node (ref "IC28") (pin "12") (pinfunction "O_12") (pintype "output"))
    )
    (net (code "56") (name "/SNDIN") (class "Default")
      (node (ref "C54") (pin "1") (pinfunction "1_1") (pintype "passive"))
      (node (ref "C57") (pin "1") (pinfunction "1_1") (pintype "passive"))
      (node (ref "D13") (pin "A") (pinfunction "A_A") (pintype "bidirectional"))
      (node (ref "D14") (pin "C") (pinfunction "C_C") (pintype "passive"))
      (node (ref "Q7") (pin "2") (pinfunction "B_2") (pintype "passive"))
      (node (ref "R40") (pin "1") (pinfunction "1_1") (pintype "passive"))
      (node (ref "R41") (pin "2") (pinfunction "2_2") (pintype "passive"))
      (node (ref "R42") (pin "2") (pinfunction "2_2") (pintype "passive"))
      (node (ref "TP3") (pin "1") (pinfunction "TP_1") (pintype "input"))
    )
    (net (code "57") (name "/{slash}INT") (class "Default")
      (node (ref "IC1") (pin "16") (pinfunction "~{INT}_16") (pintype "input"))
      (node (ref "R25") (pin "2") (pinfunction "2_2") (pintype "passive"))
      (node (ref "TP10") (pin "1") (pinfunction "TP_1") (pintype "input"))
      (node (ref "U$1") (pin "13B") (pinfunction "EDGE_13B") (pintype "bidirectional"))
    )
    (net (code "58") (name "/~{A}{slash}B") (class "Default")
      (node (ref "IC27") (pin "3") (pinfunction "O_3") (pintype "output"))
      (node (ref "IC6") (pin "1") (pinfunction "~{A}/B_1") (pintype "input"))
      (node (ref "IC7") (pin "1") (pinfunction "~{A}/B_1") (pintype "input"))
      (node (ref "R45") (pin "1") (pinfunction "1_1") (pintype "passive"))
    )
    (net (code "59") (name "/~{CAS0}") (class "Default")
      (node (ref "IC23") (pin "1") (pinfunction "~{OE}_1") (pintype "input"))
      (node (ref "IC23") (pin "16") (pinfunction "~{CAS}_16") (pintype "input"))
      (node (ref "IC24") (pin "1") (pinfunction "~{OE}_1") (pintype "input"))
      (node (ref "IC24") (pin "16") (pinfunction "~{CAS}_16") (pintype "input"))
      (node (ref "IC25") (pin "8") (pinfunction "O_8") (pintype "output"))
    )
    (net (code "60") (name "/~{CAS1}") (class "Default")
      (node (ref "IC21") (pin "1") (pinfunction "~{OE}_1") (pintype "input"))
      (node (ref "IC21") (pin "16") (pinfunction "~{CAS}_16") (pintype "input"))
      (node (ref "IC22") (pin "1") (pinfunction "~{OE}_1") (pintype "input"))
      (node (ref "IC22") (pin "16") (pinfunction "~{CAS}_16") (pintype "input"))
      (node (ref "IC25") (pin "6") (pinfunction "O_6") (pintype "output"))
    )
    (net (code "61") (name "/~{IORQGE}") (class "Default")
      (node (ref "IC3") (pin "2") (pinfunction "~{CS}_2") (pintype "input"))
      (node (ref "Q1") (pin "1") (pinfunction "E_1") (pintype "passive"))
      (node (ref "R27") (pin "2") (pinfunction "2_2") (pintype "passive"))
      (node (ref "U$1") (pin "13A") (pinfunction "EDGE_13A") (pintype "bidirectional"))
    )
    (net (code "62") (name "/~{IORQ}") (class "Default")
      (node (ref "IC1") (pin "20") (pinfunction "~{IORQ}_20") (pintype "output"))
      (node (ref "R27") (pin "1") (pinfunction "1_1") (pintype "passive"))
      (node (ref "U$1") (pin "17B") (pinfunction "EDGE_17B") (pintype "bidirectional"))
    )
    (net (code "63") (name "/~{KBD}") (class "Default")
      (node (ref "D1") (pin "C") (pinfunction "K_C") (pintype "bidirectional"))
      (node (ref "IC10") (pin "1") (pinfunction "G1_1") (pintype "input"))
      (node (ref "IC3") (pin "10") (pinfunction "~{KBD}_10") (pintype "output"))
    )
    (net (code "64") (name "/~{MREQ}") (class "Default")
      (node (ref "IC1") (pin "19") (pinfunction "~{MREQ}_19") (pintype "output"))
      (node (ref "IC2") (pin "22") (pinfunction "~{OE}_22") (pintype "input"))
      (node (ref "IC27") (pin "4") (pinfunction "I0_4") (pintype "input"))
      (node (ref "R34") (pin "1") (pinfunction "1_1") (pintype "passive"))
      (node (ref "U$1") (pin "16B") (pinfunction "EDGE_16B") (pintype "bidirectional"))
    )
    (net (code "65") (name "/~{RAS}") (class "Default")
      (node (ref "IC21") (pin "5") (pinfunction "~{RAS}_5") (pintype "input"))
      (node (ref "IC22") (pin "5") (pinfunction "~{RAS}_5") (pintype "input"))
      (node (ref "IC23") (pin "5") (pinfunction "~{RAS}_5") (pintype "input"))
      (node (ref "IC24") (pin "5") (pinfunction "~{RAS}_5") (pintype "input"))
      (node (ref "IC27") (pin "6") (pinfunction "O_6") (pintype "output"))
      (node (ref "IC27") (pin "9") (pinfunction "I0_9") (pintype "input"))
      (node (ref "R28") (pin "1") (pinfunction "1_1") (pintype "passive"))
    )
    (net (code "66") (name "/~{RD}") (class "Default")
      (node (ref "IC1") (pin "21") (pinfunction "~{RD}_21") (pintype "output"))
      (node (ref "IC2") (pin "27") (pinfunction "~{PGM}_27") (pintype "input"))
      (node (ref "IC25") (pin "2") (pinfunction "I1_2") (pintype "input"))
      (node (ref "IC3") (pin "17") (pinfunction "~{RD}_17") (pintype "input"))
      (node (ref "U$1") (pin "18B") (pinfunction "EDGE_18B") (pintype "bidirectional"))
    )
    (net (code "67") (name "/~{RESET}") (class "Default")
      (node (ref "C17") (pin "1") (pinfunction "1_1") (pintype "passive"))
      (node (ref "IC1") (pin "26") (pinfunction "~{RESET}_26") (pintype "input"))
      (node (ref "IC28") (pin "13") (pinfunction "I_13") (pintype "input"))
      (node (ref "R29") (pin "1") (pinfunction "1_1") (pintype "passive"))
      (node (ref "U$1") (pin "20A") (pinfunction "EDGE_20A") (pintype "bidirectional"))
    )
    (net (code "68") (name "/~{RFSH}") (class "Default")
      (node (ref "IC1") (pin "28") (pinfunction "~{RFSH}_28") (pintype "output"))
      (node (ref "IC26") (pin "13") (pinfunction "I1_13") (pintype "input"))
      (node (ref "IC26") (pin "2") (pinfunction "I1_2") (pintype "input"))
      (node (ref "IC5") (pin "11") (pinfunction "CLK_11") (pintype "input"))
      (node (ref "U$1") (pin "25B") (pinfunction "EDGE_25B") (pintype "bidirectional"))
    )
    (net (code "69") (name "/~{ROMCS}") (class "Default")
      (node (ref "IC2") (pin "20") (pinfunction "~{CE}_20") (pintype "input"))
      (node (ref "R26") (pin "2") (pinfunction "2_2") (pintype "passive"))
      (node (ref "TP9") (pin "1") (pinfunction "TP_1") (pintype "input"))
      (node (ref "U$1") (pin "25A") (pinfunction "EDGE_25A") (pintype "bidirectional"))
    )
    (net (code "70") (name "/~{ULAINT}") (class "Default")
      (node (ref "IC3") (pin "34") (pinfunction "~{INT}_34") (pintype "output"))
      (node (ref "R25") (pin "1") (pinfunction "1_1") (pintype "passive"))
    )
    (net (code "71") (name "/~{VCAS}") (class "Default")
      (node (ref "IC13") (pin "15") (pinfunction "~{CAS}_15") (pintype "input"))
      (node (ref "IC14") (pin "15") (pinfunction "~{CAS}_15") (pintype "input"))
      (node (ref "IC15") (pin "15") (pinfunction "~{CAS}_15") (pintype "input"))
      (node (ref "IC16") (pin "15") (pinfunction "~{CAS}_15") (pintype "input"))
      (node (ref "IC17") (pin "15") (pinfunction "~{CAS}_15") (pintype "input"))
      (node (ref "IC18") (pin "15") (pinfunction "~{CAS}_15") (pintype "input"))
      (node (ref "IC19") (pin "15") (pinfunction "~{CAS}_15") (pintype "input"))
      (node (ref "IC20") (pin "15") (pinfunction "~{CAS}_15") (pintype "input"))
      (node (ref "IC3") (pin "12") (pinfunction "~{VCAS}_12") (pintype "output"))
      (node (ref "TP5") (pin "1") (pinfunction "TP_1") (pintype "input"))
    )
    (net (code "72") (name "/~{VRAS}") (class "Default")
      (node (ref "IC13") (pin "4") (pinfunction "~{RAS}_4") (pintype "input"))
      (node (ref "IC14") (pin "4") (pinfunction "~{RAS}_4") (pintype "input"))
      (node (ref "IC15") (pin "4") (pinfunction "~{RAS}_4") (pintype "input"))
      (node (ref "IC16") (pin "4") (pinfunction "~{RAS}_4") (pintype "input"))
      (node (ref "IC17") (pin "4") (pinfunction "~{RAS}_4") (pintype "input"))
      (node (ref "IC18") (pin "4") (pinfunction "~{RAS}_4") (pintype "input"))
      (node (ref "IC19") (pin "4") (pinfunction "~{RAS}_4") (pintype "input"))
      (node (ref "IC20") (pin "4") (pinfunction "~{RAS}_4") (pintype "input"))
      (node (ref "IC3") (pin "13") (pinfunction "~{VRAS}_13") (pintype "output"))
      (node (ref "R16") (pin "2") (pinfunction "2_2") (pintype "passive"))
      (node (ref "TP4") (pin "1") (pinfunction "TP_1") (pintype "input"))
    )
    (net (code "73") (name "/~{VWR}") (class "Default")
      (node (ref "IC13") (pin "3") (pinfunction "~{WE}_3") (pintype "input"))
      (node (ref "IC14") (pin "3") (pinfunction "~{WE}_3") (pintype "input"))
      (node (ref "IC15") (pin "3") (pinfunction "~{WE}_3") (pintype "input"))
      (node (ref "IC16") (pin "3") (pinfunction "~{WE}_3") (pintype "input"))
      (node (ref "IC17") (pin "3") (pinfunction "~{WE}_3") (pintype "input"))
      (node (ref "IC18") (pin "3") (pinfunction "~{WE}_3") (pintype "input"))
      (node (ref "IC19") (pin "3") (pinfunction "~{WE}_3") (pintype "input"))
      (node (ref "IC20") (pin "3") (pinfunction "~{WE}_3") (pintype "input"))
      (node (ref "IC3") (pin "14") (pinfunction "~{VWR}_14") (pintype "output"))
      (node (ref "TP6") (pin "1") (pinfunction "TP_1") (pintype "input"))
    )
    (net (code "74") (name "/~{WR}") (class "Default")
      (node (ref "IC1") (pin "22") (pinfunction "~{WR}_22") (pintype "output"))
      (node (ref "IC21") (pin "4") (pinfunction "~{WE}_4") (pintype "input"))
      (node (ref "IC22") (pin "4") (pinfunction "~{WE}_4") (pintype "input"))
      (node (ref "IC23") (pin "4") (pinfunction "~{WE}_4") (pintype "input"))
      (node (ref "IC24") (pin "4") (pinfunction "~{WE}_4") (pintype "input"))
      (node (ref "IC25") (pin "1") (pinfunction "I0_1") (pintype "input"))
      (node (ref "IC3") (pin "16") (pinfunction "~{WR}_16") (pintype "input"))
      (node (ref "U$1") (pin "19B") (pinfunction "EDGE_19B") (pintype "bidirectional"))
    )
    (net (code "75") (name "GND") (class "Default")
      (node (ref "7805") (pin "GND") (pinfunction "GND_GND") (pintype "input"))
      (node (ref "C1") (pin "-") (pinfunction "-_-") (pintype "passive"))
      (node (ref "C10") (pin "2") (pinfunction "2_2") (pintype "passive"))
      (node (ref "C11") (pin "2") (pinfunction "2_2") (pintype "passive"))
      (node (ref "C12") (pin "1") (pinfunction "1_1") (pintype "passive"))
      (node (ref "C13") (pin "1") (pinfunction "1_1") (pintype "passive"))
      (node (ref "C14") (pin "1") (pinfunction "1_1") (pintype "passive"))
      (node (ref "C15") (pin "2") (pinfunction "2_2") (pintype "passive"))
      (node (ref "C16") (pin "2") (pinfunction "2_2") (pintype "passive"))
      (node (ref "C17") (pin "2") (pinfunction "2_2") (pintype "passive"))
      (node (ref "C18") (pin "2") (pinfunction "2_2") (pintype "passive"))
      (node (ref "C19") (pin "2") (pinfunction "2_2") (pintype "passive"))
      (node (ref "C2") (pin "-") (pinfunction "-_-") (pintype "passive"))
      (node (ref "C20") (pin "2") (pinfunction "2_2") (pintype "passive"))
      (node (ref "C21") (pin "2") (pinfunction "2_2") (pintype "passive"))
      (node (ref "C22") (pin "1") (pinfunction "1_1") (pintype "passive"))
      (node (ref "C23") (pin "2") (pinfunction "2_2") (pintype "passive"))
      (node (ref "C24") (pin "1") (pinfunction "1_1") (pintype "passive"))
      (node (ref "C25") (pin "2") (pinfunction "2_2") (pintype "passive"))
      (node (ref "C26") (pin "2") (pinfunction "2_2") (pintype "passive"))
      (node (ref "C27") (pin "2") (pinfunction "2_2") (pintype "passive"))
      (node (ref "C28") (pin "2") (pinfunction "2_2") (pintype "passive"))
      (node (ref "C29") (pin "1") (pinfunction "1_1") (pintype "passive"))
      (node (ref "C3") (pin "1") (pinfunction "1_1") (pintype "passive"))
      (node (ref "C30") (pin "2") (pinfunction "2_2") (pintype "passive"))
      (node (ref "C31") (pin "1") (pinfunction "1_1") (pintype "passive"))
      (node (ref "C32") (pin "1") (pinfunction "1_1") (pintype "passive"))
      (node (ref "C33") (pin "1") (pinfunction "1_1") (pintype "passive"))
      (node (ref "C40") (pin "1") (pinfunction "1_1") (pintype "passive"))
      (node (ref "C43") (pin "1") (pinfunction "1_1") (pintype "passive"))
      (node (ref "C44") (pin "2") (pinfunction "2_2") (pintype "passive"))
      (node (ref "C45") (pin "2") (pinfunction "2_2") (pintype "passive"))
      (node (ref "C46") (pin "2") (pinfunction "2_2") (pintype "passive"))
      (node (ref "C49") (pin "+") (pinfunction "+_+") (pintype "passive"))
      (node (ref "C50") (pin "2") (pinfunction "2_2") (pintype "passive"))
      (node (ref "C52") (pin "-") (pinfunction "-_-") (pintype "passive"))
      (node (ref "C53") (pin "-") (pinfunction "-_-") (pintype "passive"))
      (node (ref "C56") (pin "1") (pinfunction "1_1") (pintype "passive"))
      (node (ref "C57") (pin "2") (pinfunction "2_2") (pintype "passive"))
      (node (ref "C6") (pin "1") (pinfunction "1_1") (pintype "passive"))
      (node (ref "C8") (pin "1") (pinfunction "1_1") (pintype "passive"))
      (node (ref "D14") (pin "A") (pinfunction "A_A") (pintype "passive"))
      (node (ref "D16") (pin "A") (pinfunction "A_A") (pintype "bidirectional"))
      (node (ref "D18") (pin "A") (pinfunction "A_A") (pintype "bidirectional"))
      (node (ref "D20") (pin "C") (pinfunction "K_C") (pintype "bidirectional"))
      (node (ref "D21") (pin "C") (pinfunction "K_C") (pintype "bidirectional"))
      (node (ref "D24") (pin "A") (pinfunction "A_A") (pintype "bidirectional"))
      (node (ref "EAR") (pin "RING") (pinfunction "SHIELD_RING") (pintype "passive"))
      (node (ref "IC1") (pin "29") (pinfunction "GND_29") (pintype "power_in"))
      (node (ref "IC10") (pin "15") (pinfunction "G2_15") (pintype "input"))
      (node (ref "IC10") (pin "8") (pinfunction "GND_8") (pintype "power_in"))
      (node (ref "IC11") (pin "10") (pinfunction "GND_10") (pintype "power_in"))
      (node (ref "IC12") (pin "5") (pinfunction "GND_5") (pintype "power_in"))
      (node (ref "IC13") (pin "16") (pinfunction "VSS_16") (pintype "power_in"))
      (node (ref "IC14") (pin "16") (pinfunction "VSS_16") (pintype "power_in"))
      (node (ref "IC15") (pin "16") (pinfunction "VSS_16") (pintype "power_in"))
      (node (ref "IC16") (pin "16") (pinfunction "VSS_16") (pintype "power_in"))
      (node (ref "IC17") (pin "16") (pinfunction "VSS_16") (pintype "power_in"))
      (node (ref "IC18") (pin "16") (pinfunction "VSS_16") (pintype "power_in"))
      (node (ref "IC19") (pin "16") (pinfunction "VSS_16") (pintype "power_in"))
      (node (ref "IC2") (pin "14") (pinfunction "GND_14") (pintype "power_in"))
      (node (ref "IC20") (pin "16") (pinfunction "VSS_16") (pintype "power_in"))
      (node (ref "IC21") (pin "18") (pinfunction "GND_18") (pintype "power_in"))
      (node (ref "IC22") (pin "18") (pinfunction "GND_18") (pintype "power_in"))
      (node (ref "IC23") (pin "18") (pinfunction "GND_18") (pintype "power_in"))
      (node (ref "IC24") (pin "18") (pinfunction "GND_18") (pintype "power_in"))
      (node (ref "IC25") (pin "7") (pinfunction "GND_7") (pintype "power_in"))
      (node (ref "IC26") (pin "7") (pinfunction "GND_7") (pintype "power_in"))
      (node (ref "IC27") (pin "5") (pinfunction "I1_5") (pintype "input"))
      (node (ref "IC27") (pin "7") (pinfunction "GND_7") (pintype "power_in"))
      (node (ref "IC28") (pin "7") (pinfunction "GND_7") (pintype "power_in"))
      (node (ref "IC3") (pin "20") (pinfunction "GND_20") (pintype "power_in"))
      (node (ref "IC4") (pin "7") (pinfunction "GND_7") (pintype "power_in"))
      (node (ref "IC5") (pin "7") (pinfunction "GND_7") (pintype "power_in"))
      (node (ref "IC6") (pin "15") (pinfunction "G_15") (pintype "input"))
      (node (ref "IC6") (pin "8") (pinfunction "GND_8") (pintype "power_in"))
      (node (ref "IC7") (pin "15") (pinfunction "G_15") (pintype "input"))
      (node (ref "IC7") (pin "8") (pinfunction "GND_8") (pintype "power_in"))
      (node (ref "IC8") (pin "15") (pinfunction "G_15") (pintype "input"))
      (node (ref "IC8") (pin "8") (pinfunction "GND_8") (pintype "power_in"))
      (node (ref "IC9") (pin "15") (pinfunction "G_15") (pintype "input"))
      (node (ref "IC9") (pin "8") (pinfunction "GND_8") (pintype "power_in"))
      (node (ref "MIC") (pin "RING") (pinfunction "SHIELD_RING") (pintype "passive"))
      (node (ref "Q2") (pin "1") (pinfunction "E_1") (pintype "passive"))
      (node (ref "Q4") (pin "1") (pinfunction "E_1") (pintype "passive"))
      (node (ref "Q6") (pin "C") (pinfunction "C_C") (pintype "passive"))
      (node (ref "Q7") (pin "1") (pinfunction "E_1") (pintype "passive"))
      (node (ref "R33") (pin "2") (pinfunction "2_2") (pintype "passive"))
      (node (ref "R41") (pin "1") (pinfunction "1_1") (pintype "passive"))
      (node (ref "R47") (pin "1") (pinfunction "1_1") (pintype "passive"))
      (node (ref "R50") (pin "1") (pinfunction "1_1") (pintype "passive"))
      (node (ref "R53") (pin "2") (pinfunction "2_2") (pintype "passive"))
      (node (ref "R55") (pin "2") (pinfunction "2_2") (pintype "passive"))
      (node (ref "R60") (pin "2") (pinfunction "2_2") (pintype "passive"))
      (node (ref "R65") (pin "2") (pinfunction "2_2") (pintype "passive"))
      (node (ref "R69") (pin "1") (pinfunction "1_1") (pintype "passive"))
      (node (ref "R70") (pin "1") (pinfunction "1_1") (pintype "passive"))
      (node (ref "R73_") (pin "2") (pinfunction "2_2") (pintype "passive"))
      (node (ref "U$1") (pin "14A") (pinfunction "EDGE_14A") (pintype "bidirectional"))
      (node (ref "U$1") (pin "6A") (pinfunction "EDGE_6A") (pintype "bidirectional"))
      (node (ref "U$1") (pin "7A") (pinfunction "EDGE_7A") (pintype "bidirectional"))
      (node (ref "X2") (pin "RING") (pinfunction "SHIELD_RING") (pintype "passive"))
    )
    (net (code "76") (name "Net-(C5-Pad1)") (class "Default")
      (node (ref "C5") (pin "1") (pinfunction "1_1") (pintype "passive"))
      (node (ref "R42") (pin "1") (pinfunction "1_1") (pintype "passive"))
    )
    (net (code "77") (name "Net-(C5-Pad2)") (class "Default")
      (node (ref "C5") (pin "2") (pinfunction "2_2") (pintype "passive"))
      (node (ref "EAR") (pin "NC") (pinfunction "NC_NC") (pintype "passive"))
      (node (ref "EAR") (pin "TIP") (pinfunction "TIP_TIP") (pintype "passive"))
      (node (ref "R70") (pin "2") (pinfunction "2_2") (pintype "passive"))
    )
    (net (code "78") (name "Net-(C7-Pad1)") (class "Default")
      (node (ref "C7") (pin "1") (pinfunction "1_1") (pintype "passive"))
      (node (ref "XTAL") (pin "2") (pinfunction "2_2") (pintype "passive"))
    )
    (net (code "79") (name "Net-(C8-Pad2)") (class "Default")
      (node (ref "C8") (pin "2") (pinfunction "2_2") (pintype "passive"))
      (node (ref "Q3") (pin "B") (pinfunction "B_B") (pintype "passive"))
      (node (ref "R44") (pin "2") (pinfunction "2_2") (pintype "passive"))
      (node (ref "XTAL") (pin "1") (pinfunction "1_1") (pintype "passive"))
    )
    (net (code "80") (name "Net-(C34-Pad2)") (class "Default")
      (node (ref "C34") (pin "2") (pinfunction "2_2") (pintype "passive"))
      (node (ref "R52") (pin "2") (pinfunction "2_2") (pintype "passive"))
    )
    (net (code "81") (name "Net-(C36-Pad2)") (class "Default")
      (node (ref "C36") (pin "2") (pinfunction "2_2") (pintype "passive"))
      (node (ref "C54") (pin "2") (pinfunction "2_2") (pintype "passive"))
      (node (ref "C55") (pin "1") (pinfunction "1_1") (pintype "passive"))
      (node (ref "D25_") (pin "A") (pinfunction "A_A") (pintype "bidirectional"))
      (node (ref "R53") (pin "1") (pinfunction "1_1") (pintype "passive"))
      (node (ref "R54") (pin "2") (pinfunction "2_2") (pintype "passive"))
    )
    (net (code "82") (name "Net-(C37-Pad1)") (class "Default")
      (node (ref "C37") (pin "1") (pinfunction "1_1") (pintype "passive"))
      (node (ref "C38") (pin "2") (pinfunction "2_2") (pintype "passive"))
      (node (ref "R55") (pin "1") (pinfunction "1_1") (pintype "passive"))
    )
    (net (code "83") (name "Net-(C38-Pad1)") (class "Default")
      (node (ref "C38") (pin "1") (pinfunction "1_1") (pintype "passive"))
      (node (ref "C39") (pin "2") (pinfunction "2_2") (pintype "passive"))
      (node (ref "R56") (pin "1") (pinfunction "1_1") (pintype "passive"))
    )
    (net (code "84") (name "Net-(C39-Pad1)") (class "Default")
      (node (ref "C39") (pin "1") (pinfunction "1_1") (pintype "passive"))
      (node (ref "L2") (pin "2") (pinfunction "2_2") (pintype "passive"))
    )
    (net (code "85") (name "Net-(C49-Pad-)") (class "Default")
      (node (ref "C49") (pin "-") (pinfunction "-_-") (pintype "passive"))
      (node (ref "D19") (pin "A") (pinfunction "A_A") (pintype "bidirectional"))
      (node (ref "R67") (pin "2") (pinfunction "2_2") (pintype "passive"))
    )
    (net (code "86") (name "Net-(C56-Pad2)") (class "Default")
      (node (ref "C56") (pin "2") (pinfunction "2_2") (pintype "passive"))
      (node (ref "L2") (pin "1") (pinfunction "1_1") (pintype "passive"))
      (node (ref "R71") (pin "1") (pinfunction "1_1") (pintype "passive"))
      (node (ref "R72") (pin "2") (pinfunction "2_2") (pintype "passive"))
    )
    (net (code "87") (name "Net-(D2-PadA)") (class "Default")
      (node (ref "D2") (pin "A") (pinfunction "A_A") (pintype "bidirectional"))
      (node (ref "KB2") (pin "3") (pinfunction "3_3") (pintype "passive"))
    )
    (net (code "88") (name "Net-(D3-PadA)") (class "Default")
      (node (ref "D3") (pin "A") (pinfunction "A_A") (pintype "bidirectional"))
      (node (ref "KB2") (pin "6") (pinfunction "6_6") (pintype "passive"))
    )
    (net (code "89") (name "Net-(D4-PadA)") (class "Default")
      (node (ref "D4") (pin "A") (pinfunction "A_A") (pintype "bidirectional"))
      (node (ref "KB2") (pin "7") (pinfunction "7_7") (pintype "passive"))
    )
    (net (code "90") (name "Net-(D7-PadA)") (class "Default")
      (node (ref "D7") (pin "A") (pinfunction "A_A") (pintype "bidirectional"))
      (node (ref "KB2") (pin "4") (pinfunction "4_4") (pintype "passive"))
    )
    (net (code "91") (name "Net-(D8-PadA)") (class "Default")
      (node (ref "D8") (pin "A") (pinfunction "A_A") (pintype "bidirectional"))
      (node (ref "KB2") (pin "2") (pinfunction "2_2") (pintype "passive"))
    )
    (net (code "92") (name "Net-(D9-PadA)") (class "Default")
      (node (ref "D9") (pin "A") (pinfunction "A_A") (pintype "bidirectional"))
      (node (ref "KB2") (pin "1") (pinfunction "1_1") (pintype "passive"))
    )
    (net (code "93") (name "Net-(D11-K)") (class "Default")
      (node (ref "D11") (pin "C") (pinfunction "K_C") (pintype "bidirectional"))
      (node (ref "D12") (pin "C") (pinfunction "K_C") (pintype "bidirectional"))
      (node (ref "IC27") (pin "11") (pinfunction "O_11") (pintype "output"))
      (node (ref "R26") (pin "1") (pinfunction "1_1") (pintype "passive"))
      (node (ref "R33") (pin "1") (pinfunction "1_1") (pintype "passive"))
    )
    (net (code "94") (name "Net-(D16-K)") (class "Default")
      (node (ref "C36") (pin "1") (pinfunction "1_1") (pintype "passive"))
      (node (ref "D15") (pin "A") (pinfunction "A_A") (pintype "bidirectional"))
      (node (ref "D16") (pin "C") (pinfunction "K_C") (pintype "bidirectional"))
      (node (ref "IC3") (pin "24") (pinfunction "BEEP_24") (pintype "output"))
      (node (ref "TP7") (pin "1") (pinfunction "TP_1") (pintype "input"))
    )
    (net (code "95") (name "Net-(D19-K)") (class "Default")
      (node (ref "C48") (pin "2") (pinfunction "2_2") (pintype "passive"))
      (node (ref "D19") (pin "C") (pinfunction "K_C") (pintype "bidirectional"))
      (node (ref "D20") (pin "A") (pinfunction "A_A") (pintype "bidirectional"))
    )
    (net (code "96") (name "Net-(D22-K)") (class "Default")
      (node (ref "C51") (pin "2") (pinfunction "2_2") (pintype "passive"))
      (node (ref "D22") (pin "C") (pinfunction "K_C") (pintype "bidirectional"))
      (node (ref "D23") (pin "A") (pinfunction "A_A") (pintype "bidirectional"))
    )
    (net (code "97") (name "Net-(D23-K)") (class "Default")
      (node (ref "C52") (pin "+") (pinfunction "+_+") (pintype "passive"))
      (node (ref "D23") (pin "C") (pinfunction "K_C") (pintype "bidirectional"))
      (node (ref "R68") (pin "2") (pinfunction "2_2") (pintype "passive"))
    )
    (net (code "98") (name "Net-(D27-K)") (class "Default")
      (node (ref "D25") (pin "C") (pinfunction "C_C") (pintype "passive"))
      (node (ref "D26") (pin "C") (pinfunction "C_C") (pintype "passive"))
      (node (ref "D27") (pin "C") (pinfunction "K_C") (pintype "bidirectional"))
      (node (ref "IC3") (pin "18") (pinfunction "BRIGHT_18") (pintype "output"))
    )
    (net (code "99") (name "Net-(IC1-CLK)") (class "Default")
      (node (ref "IC1") (pin "6") (pinfunction "CLK_6") (pintype "input"))
      (node (ref "Q2") (pin "3") (pinfunction "C_3") (pintype "passive"))
      (node (ref "R48") (pin "1") (pinfunction "1_1") (pintype "passive"))
      (node (ref "TP1") (pin "1") (pinfunction "TP_1") (pintype "input"))
    )
    (net (code "100") (name "Net-(IC1-~{BUSAK})") (class "Default")
      (node (ref "IC1") (pin "23") (pinfunction "~{BUSAK}_23") (pintype "output"))
      (node (ref "U$1") (pin "26A") (pinfunction "EDGE_26A") (pintype "bidirectional"))
    )
    (net (code "101") (name "Net-(IC1-~{BUSRQ})") (class "Default")
      (node (ref "IC1") (pin "25") (pinfunction "~{BUSRQ}_25") (pintype "input"))
      (node (ref "R30") (pin "2") (pinfunction "2_2") (pintype "passive"))
      (node (ref "U$1") (pin "19A") (pinfunction "EDGE_19A") (pintype "bidirectional"))
    )
    (net (code "102") (name "Net-(IC1-~{HALT})") (class "Default")
      (node (ref "IC1") (pin "18") (pinfunction "~{HALT}_18") (pintype "output"))
      (node (ref "U$1") (pin "15B") (pinfunction "EDGE_15B") (pintype "bidirectional"))
    )
    (net (code "103") (name "Net-(IC1-~{M1})") (class "Default")
      (node (ref "IC1") (pin "27") (pinfunction "~{M1}_27") (pintype "output"))
      (node (ref "U$1") (pin "24B") (pinfunction "EDGE_24B") (pintype "bidirectional"))
    )
    (net (code "104") (name "Net-(IC1-~{NMI})") (class "Default")
      (node (ref "IC1") (pin "17") (pinfunction "~{NMI}_17") (pintype "input"))
      (node (ref "R31") (pin "2") (pinfunction "2_2") (pintype "passive"))
      (node (ref "U$1") (pin "14B") (pinfunction "EDGE_14B") (pintype "bidirectional"))
    )
    (net (code "105") (name "Net-(IC1-~{WAIT})") (class "Default")
      (node (ref "IC1") (pin "24") (pinfunction "~{WAIT}_24") (pintype "input"))
      (node (ref "R32") (pin "2") (pinfunction "2_2") (pintype "passive"))
      (node (ref "U$1") (pin "21B") (pinfunction "EDGE_21B") (pintype "bidirectional"))
    )
    (net (code "106") (name "Net-(IC3-MIC)") (class "Default")
      (node (ref "IC3") (pin "23") (pinfunction "MIC_23") (pintype "output"))
      (node (ref "R46") (pin "2") (pinfunction "2_2") (pintype "passive"))
    )
    (net (code "107") (name "Net-(IC4B-D)") (class "Default")
      (node (ref "IC4") (pin "12") (pinfunction "D_12") (pintype "input"))
      (node (ref "IC4") (pin "8") (pinfunction "~{Q}_8") (pintype "output"))
    )
    (net (code "108") (name "Net-(IC5A-CLK)") (class "Default")
      (node (ref "IC5") (pin "3") (pinfunction "CLK_3") (pintype "input"))
      (node (ref "IC5") (pin "9") (pinfunction "Q_9") (pintype "output"))
    )
    (net (code "109") (name "Net-(IC5A-D)") (class "Default")
      (node (ref "IC5") (pin "2") (pinfunction "D_2") (pintype "input"))
      (node (ref "IC5") (pin "6") (pinfunction "~{Q}_6") (pintype "output"))
    )
    (net (code "110") (name "Net-(IC8A-1Y)") (class "Default")
      (node (ref "IC8") (pin "4") (pinfunction "1Y_4") (pintype "output"))
      (node (ref "R15") (pin "2") (pinfunction "2_2") (pintype "passive"))
    )
    (net (code "111") (name "Net-(IC8A-2Y)") (class "Default")
      (node (ref "IC8") (pin "7") (pinfunction "2Y_7") (pintype "output"))
      (node (ref "R14") (pin "2") (pinfunction "2_2") (pintype "passive"))
    )
    (net (code "112") (name "Net-(IC8A-3Y)") (class "Default")
      (node (ref "IC8") (pin "9") (pinfunction "3Y_9") (pintype "output"))
      (node (ref "R12") (pin "2") (pinfunction "2_2") (pintype "passive"))
    )
    (net (code "113") (name "Net-(IC8A-4Y)") (class "Default")
      (node (ref "IC8") (pin "12") (pinfunction "4Y_12") (pintype "output"))
      (node (ref "R13") (pin "2") (pinfunction "2_2") (pintype "passive"))
    )
    (net (code "114") (name "Net-(IC8A-~{A}{slash}B)") (class "Default")
      (node (ref "IC8") (pin "1") (pinfunction "~{A}/B_1") (pintype "input"))
      (node (ref "IC9") (pin "1") (pinfunction "~{A}/B_1") (pintype "input"))
      (node (ref "R16") (pin "1") (pinfunction "1_1") (pintype "passive"))
    )
    (net (code "115") (name "Net-(IC9A-2Y)") (class "Default")
      (node (ref "IC9") (pin "7") (pinfunction "2Y_7") (pintype "output"))
      (node (ref "R11") (pin "2") (pinfunction "2_2") (pintype "passive"))
    )
    (net (code "116") (name "Net-(IC9A-3Y)") (class "Default")
      (node (ref "IC9") (pin "9") (pinfunction "3Y_9") (pintype "output"))
      (node (ref "R9") (pin "2") (pinfunction "2_2") (pintype "passive"))
    )
    (net (code "117") (name "Net-(IC9A-4Y)") (class "Default")
      (node (ref "IC9") (pin "12") (pinfunction "4Y_12") (pintype "output"))
      (node (ref "R10") (pin "2") (pinfunction "2_2") (pintype "passive"))
    )
    (net (code "118") (name "Net-(IC10A-A1)") (class "Default")
      (node (ref "IC10") (pin "2") (pinfunction "A1_2") (pintype "input"))
      (node (ref "KB1") (pin "5") (pinfunction "5_5") (pintype "passive"))
      (node (ref "P") (pin "6") (pinfunction "M_6") (pintype "passive"))
      (node (ref "R39") (pin "2") (pinfunction "2_2") (pintype "passive"))
    )
    (net (code "119") (name "Net-(IC10A-A2)") (class "Default")
      (node (ref "IC10") (pin "4") (pinfunction "A2_4") (pintype "input"))
      (node (ref "KB1") (pin "4") (pinfunction "4_4") (pintype "passive"))
      (node (ref "P") (pin "1") (pinfunction "M_1") (pintype "passive"))
      (node (ref "R38") (pin "2") (pinfunction "2_2") (pintype "passive"))
    )
    (net (code "120") (name "Net-(IC10A-A3)") (class "Default")
      (node (ref "IC10") (pin "6") (pinfunction "A3_6") (pintype "input"))
      (node (ref "KB1") (pin "3") (pinfunction "3_3") (pintype "passive"))
      (node (ref "P") (pin "2") (pinfunction "M_2") (pintype "passive"))
      (node (ref "R35") (pin "2") (pinfunction "2_2") (pintype "passive"))
    )
    (net (code "121") (name "Net-(IC10A-A4)") (class "Default")
      (node (ref "IC10") (pin "10") (pinfunction "A4_10") (pintype "input"))
      (node (ref "KB1") (pin "2") (pinfunction "2_2") (pintype "passive"))
      (node (ref "P") (pin "4") (pinfunction "M_4") (pintype "passive"))
      (node (ref "R36") (pin "2") (pinfunction "2_2") (pintype "passive"))
    )
    (net (code "122") (name "Net-(IC10A-A5)") (class "Default")
      (node (ref "IC10") (pin "12") (pinfunction "A5_12") (pintype "input"))
      (node (ref "KB1") (pin "1") (pinfunction "1_1") (pintype "passive"))
      (node (ref "P") (pin "3") (pinfunction "M_3") (pintype "passive"))
      (node (ref "R37") (pin "2") (pinfunction "2_2") (pintype "passive"))
    )
    (net (code "123") (name "Net-(IC10A-A6)") (class "Default")
      (node (ref "IC10") (pin "14") (pinfunction "A6_14") (pintype "input"))
      (node (ref "Q7") (pin "3") (pinfunction "C_3") (pintype "passive"))
      (node (ref "R74_") (pin "1") (pinfunction "1_1") (pintype "passive"))
    )
    (net (code "124") (name "Net-(IC11-B-Y)") (class "Default")
      (node (ref "C45") (pin "1") (pinfunction "1_1") (pintype "passive"))
      (node (ref "IC11") (pin "4") (pinfunction "B-Y_4") (pintype "output"))
      (node (ref "IC12") (pin "4") (pinfunction "B-Y_4") (pintype "input"))
    )
    (net (code "125") (name "Net-(IC11-B1)") (class "Default")
      (node (ref "IC11") (pin "17") (pinfunction "B3_17") (pintype "input"))
      (node (ref "IC11") (pin "19") (pinfunction "B1_19") (pintype "input"))
      (node (ref "IC3") (pin "22") (pinfunction "BLUE_22") (pintype "output"))
      (node (ref "R75") (pin "2") (pinfunction "2_2") (pintype "passive"))
    )
    (net (code "126") (name "Net-(IC11-B2)") (class "Default")
      (node (ref "D27") (pin "A") (pinfunction "A_A") (pintype "bidirectional"))
      (node (ref "IC11") (pin "18") (pinfunction "B2_18") (pintype "input"))
      (node (ref "R75") (pin "1") (pinfunction "1_1") (pintype "passive"))
    )
    (net (code "127") (name "Net-(IC11-BLANK)") (class "Default")
      (node (ref "IC11") (pin "8") (pinfunction "SYNC_8") (pintype "input"))
      (node (ref "IC11") (pin "9") (pinfunction "BLANK_9") (pintype "input"))
      (node (ref "IC3") (pin "33") (pinfunction "SYNC_33") (pintype "output"))
      (node (ref "TP8") (pin "1") (pinfunction "TP_1") (pintype "input"))
    )
    (net (code "128") (name "Net-(IC11-CREF)") (class "Default")
      (node (ref "C46") (pin "1") (pinfunction "1_1") (pintype "passive"))
      (node (ref "IC11") (pin "7") (pinfunction "CREF_7") (pintype "input"))
      (node (ref "IC12") (pin "12") (pinfunction "Y_12") (pintype "input"))
    )
    (net (code "129") (name "Net-(IC11-G1)") (class "Default")
      (node (ref "IC11") (pin "14") (pinfunction "G3_14") (pintype "input"))
      (node (ref "IC11") (pin "16") (pinfunction "G1_16") (pintype "input"))
      (node (ref "IC3") (pin "19") (pinfunction "GREEN_19") (pintype "output"))
      (node (ref "R73") (pin "2") (pinfunction "2_2") (pintype "passive"))
    )
    (net (code "130") (name "Net-(IC11-G2)") (class "Default")
      (node (ref "D25") (pin "A") (pinfunction "A_A") (pintype "passive"))
      (node (ref "IC11") (pin "15") (pinfunction "G2_15") (pintype "input"))
      (node (ref "R73") (pin "1") (pinfunction "1_1") (pintype "passive"))
    )
    (net (code "131") (name "Net-(IC11-GATE)") (class "Default")
      (node (ref "IC11") (pin "1") (pinfunction "GATE_1") (pintype "input"))
      (node (ref "IC28") (pin "6") (pinfunction "O_6") (pintype "output"))
    )
    (net (code "132") (name "Net-(IC11-H{slash}2)") (class "Default")
      (node (ref "IC11") (pin "2") (pinfunction "H/2_2") (pintype "input"))
      (node (ref "IC4") (pin "9") (pinfunction "Q_9") (pintype "output"))
    )
    (net (code "133") (name "Net-(IC11-R-Y)") (class "Default")
      (node (ref "C44") (pin "1") (pinfunction "1_1") (pintype "passive"))
      (node (ref "IC11") (pin "3") (pinfunction "R-Y_3") (pintype "output"))
      (node (ref "IC12") (pin "2") (pinfunction "R-Y_2") (pintype "input"))
    )
    (net (code "134") (name "Net-(IC11-R1)") (class "Default")
      (node (ref "IC11") (pin "11") (pinfunction "R3_11") (pintype "input"))
      (node (ref "IC11") (pin "13") (pinfunction "R1_13") (pintype "input"))
      (node (ref "IC3") (pin "21") (pinfunction "RED_21") (pintype "output"))
      (node (ref "R74") (pin "2") (pinfunction "2_2") (pintype "passive"))
    )
    (net (code "135") (name "Net-(IC11-R2)") (class "Default")
      (node (ref "D26") (pin "A") (pinfunction "A_A") (pintype "passive"))
      (node (ref "IC11") (pin "12") (pinfunction "R2_12") (pintype "input"))
      (node (ref "R74") (pin "1") (pinfunction "1_1") (pintype "passive"))
    )
    (net (code "136") (name "Net-(IC11-Y)") (class "Default")
      (node (ref "IC11") (pin "6") (pinfunction "Y_6") (pintype "output"))
      (node (ref "R63") (pin "2") (pinfunction "2_2") (pintype "passive"))
    )
    (net (code "137") (name "Net-(IC12-CHB_O)") (class "Default")
      (node (ref "C42") (pin "1") (pinfunction "1_1") (pintype "passive"))
      (node (ref "IC12") (pin "10") (pinfunction "CHB_O_10") (pintype "input"))
      (node (ref "R59") (pin "2") (pinfunction "2_2") (pintype "passive"))
    )
    (net (code "138") (name "Net-(IC12-CR_LAG)") (class "Default")
      (node (ref "C40") (pin "2") (pinfunction "2_2") (pintype "passive"))
      (node (ref "IC12") (pin "18") (pinfunction "CR_LAG_18") (pintype "output"))
      (node (ref "R56") (pin "2") (pinfunction "2_2") (pintype "passive"))
    )
    (net (code "139") (name "Net-(IC12-CR_LEAD)") (class "Default")
      (node (ref "C37") (pin "2") (pinfunction "2_2") (pintype "passive"))
      (node (ref "IC12") (pin "1") (pinfunction "CR_LEAD_1") (pintype "input"))
    )
    (net (code "140") (name "Net-(IC12-CR_OSC)") (class "Default")
      (node (ref "IC12") (pin "17") (pinfunction "CR_OSC_17") (pintype "input"))
      (node (ref "R72") (pin "1") (pinfunction "1_1") (pintype "passive"))
      (node (ref "R73_") (pin "1") (pinfunction "1_1") (pintype "passive"))
    )
    (net (code "141") (name "Net-(IC12-CR_SUBC)") (class "Default")
      (node (ref "C34") (pin "1") (pinfunction "1_1") (pintype "passive"))
      (node (ref "IC12") (pin "13") (pinfunction "CR_SUBC_13") (pintype "input"))
      (node (ref "R63") (pin "1") (pinfunction "1_1") (pintype "passive"))
    )
    (net (code "142") (name "Net-(IC12-SNDTK)") (class "Default")
      (node (ref "D25_") (pin "K") (pinfunction "K_K") (pintype "bidirectional"))
      (node (ref "IC12") (pin "15") (pinfunction "SNDTK_15") (pintype "input"))
      (node (ref "L1") (pin "4") (pinfunction "E_4") (pintype "passive"))
      (node (ref "R52") (pin "1") (pinfunction "1_1") (pintype "passive"))
    )
    (net (code "143") (name "Net-(IC12-TNKA1)") (class "Default")
      (node (ref "IC12") (pin "8") (pinfunction "TNKA1_8") (pintype "output"))
      (node (ref "IC12") (pin "9") (pinfunction "TNKA2_9") (pintype "input"))
    )
    (net (code "144") (name "Net-(IC12-TNKB1)") (class "Default")
      (node (ref "C41") (pin "2") (pinfunction "2_2") (pintype "passive"))
      (node (ref "IC12") (pin "6") (pinfunction "TNKB1_6") (pintype "output"))
      (node (ref "L3") (pin "1") (pinfunction "1_1") (pintype "passive"))
      (node (ref "R57") (pin "2") (pinfunction "2_2") (pintype "passive"))
    )
    (net (code "145") (name "Net-(IC12-TNKB2)") (class "Default")
      (node (ref "C41") (pin "1") (pinfunction "1_1") (pintype "passive"))
      (node (ref "IC12") (pin "7") (pinfunction "TNKB2_7") (pintype "input"))
      (node (ref "L3") (pin "2") (pinfunction "2_2") (pintype "passive"))
      (node (ref "R58") (pin "2") (pinfunction "2_2") (pintype "passive"))
    )
    (net (code "146") (name "Net-(IC25A-O)") (class "Default")
      (node (ref "IC25") (pin "12") (pinfunction "I0_12") (pintype "input"))
      (node (ref "IC25") (pin "3") (pinfunction "O_3") (pintype "output"))
    )
    (net (code "147") (name "Net-(IC25B-I1)") (class "Default")
      (node (ref "IC25") (pin "10") (pinfunction "I1_10") (pintype "input"))
      (node (ref "IC25") (pin "5") (pinfunction "I1_5") (pintype "input"))
      (node (ref "IC28") (pin "4") (pinfunction "O_4") (pintype "output"))
    )
    (net (code "148") (name "Net-(IC25C-I0)") (class "Default")
      (node (ref "IC25") (pin "9") (pinfunction "I0_9") (pintype "input"))
      (node (ref "IC28") (pin "2") (pinfunction "O_2") (pintype "output"))
    )
    (net (code "149") (name "Net-(IC25D-O)") (class "Default")
      (node (ref "IC25") (pin "11") (pinfunction "O_11") (pintype "output"))
      (node (ref "IC27") (pin "1") (pinfunction "I0_1") (pintype "input"))
    )
    (net (code "150") (name "Net-(IC26A-O)") (class "Default")
      (node (ref "IC26") (pin "3") (pinfunction "O_3") (pintype "output"))
      (node (ref "IC26") (pin "4") (pinfunction "I0_4") (pintype "input"))
    )
    (net (code "151") (name "Net-(IC26B-I1)") (class "Default")
      (node (ref "IC26") (pin "5") (pinfunction "I1_5") (pintype "input"))
      (node (ref "IC5") (pin "5") (pinfunction "Q_5") (pintype "output"))
    )
    (net (code "152") (name "Net-(IC26B-O)") (class "Default")
      (node (ref "IC26") (pin "6") (pinfunction "O_6") (pintype "output"))
      (node (ref "IC26") (pin "9") (pinfunction "I0_9") (pintype "input"))
    )
    (net (code "153") (name "Net-(IC26C-I1)") (class "Default")
      (node (ref "IC26") (pin "10") (pinfunction "I1_10") (pintype "input"))
      (node (ref "IC26") (pin "11") (pinfunction "O_11") (pintype "output"))
    )
    (net (code "154") (name "Net-(IC27A-I1)") (class "Default")
      (node (ref "C10") (pin "1") (pinfunction "1_1") (pintype "passive"))
      (node (ref "IC27") (pin "2") (pinfunction "I1_2") (pintype "input"))
      (node (ref "R28") (pin "2") (pinfunction "2_2") (pintype "passive"))
    )
    (net (code "155") (name "Net-(IC27C-I1)") (class "Default")
      (node (ref "C11") (pin "1") (pinfunction "1_1") (pintype "passive"))
      (node (ref "IC27") (pin "10") (pinfunction "I1_10") (pintype "input"))
      (node (ref "R45") (pin "2") (pinfunction "2_2") (pintype "passive"))
    )
    (net (code "156") (name "Net-(IC27C-O)") (class "Default")
      (node (ref "IC27") (pin "8") (pinfunction "O_8") (pintype "output"))
      (node (ref "IC28") (pin "3") (pinfunction "I_3") (pintype "input"))
    )
    (net (code "157") (name "Net-(IC28C-I)") (class "Default")
      (node (ref "IC28") (pin "5") (pinfunction "I_5") (pintype "input"))
      (node (ref "IC3") (pin "35") (pinfunction "GATE_35") (pintype "output"))
      (node (ref "IC4") (pin "11") (pinfunction "CLK_11") (pintype "input"))
    )
    (net (code "158") (name "Net-(IC28D-I)") (class "Default")
      (node (ref "C6") (pin "2") (pinfunction "2_2") (pintype "passive"))
      (node (ref "C7") (pin "2") (pinfunction "2_2") (pintype "passive"))
      (node (ref "IC28") (pin "9") (pinfunction "I_9") (pintype "input"))
      (node (ref "Q3") (pin "C") (pinfunction "C_C") (pintype "passive"))
      (node (ref "R43") (pin "1") (pinfunction "1_1") (pintype "passive"))
      (node (ref "R44") (pin "1") (pinfunction "1_1") (pintype "passive"))
    )
    (net (code "159") (name "Net-(IC28D-O)") (class "Default")
      (node (ref "IC28") (pin "11") (pinfunction "I_11") (pintype "input"))
      (node (ref "IC28") (pin "8") (pinfunction "O_8") (pintype "output"))
      (node (ref "JP") (pin "3") (pinfunction "3_3") (pintype "passive"))
    )
    (net (code "160") (name "Net-(IC28E-O)") (class "Default")
      (node (ref "IC28") (pin "10") (pinfunction "O_10") (pintype "output"))
      (node (ref "IC3") (pin "11") (pinfunction "CLK_11") (pintype "input"))
      (node (ref "JP") (pin "1") (pinfunction "1_1") (pintype "passive"))
      (node (ref "JP") (pin "2") (pinfunction "2_2") (pintype "passive"))
      (node (ref "TP2") (pin "1") (pinfunction "TP_1") (pintype "input"))
    )
    (net (code "161") (name "Net-(MIC-PadNC)") (class "Default")
      (node (ref "MIC") (pin "NC") (pinfunction "NC_NC") (pintype "passive"))
      (node (ref "MIC") (pin "TIP") (pinfunction "TIP_TIP") (pintype "passive"))
      (node (ref "R46") (pin "1") (pinfunction "1_1") (pintype "passive"))
      (node (ref "R69") (pin "2") (pinfunction "2_2") (pintype "passive"))
    )
    (net (code "162") (name "Net-(PE-M)") (class "Default")
      (node (ref "D6") (pin "A") (pinfunction "A_A") (pintype "bidirectional"))
      (node (ref "KB2") (pin "5") (pinfunction "5_5") (pintype "passive"))
      (node (ref "P") (pin "5") (pinfunction "M_5") (pintype "passive"))
      (node (ref "P") (pin "8") (pinfunction "M_8") (pintype "passive"))
      (node (ref "P") (pin "9") (pinfunction "M_9") (pintype "passive"))
    )
    (net (code "163") (name "Net-(PG-M)") (class "Default")
      (node (ref "D5") (pin "A") (pinfunction "A_A") (pintype "bidirectional"))
      (node (ref "KB2") (pin "8") (pinfunction "8_8") (pintype "passive"))
      (node (ref "P") (pin "7") (pinfunction "M_7") (pintype "passive"))
    )
    (net (code "164") (name "Net-(Q2-B)") (class "Default")
      (node (ref "C9") (pin "1") (pinfunction "1_1") (pintype "passive"))
      (node (ref "Q2") (pin "2") (pinfunction "B_2") (pintype "passive"))
      (node (ref "R49") (pin "1") (pinfunction "1_1") (pintype "passive"))
      (node (ref "R50") (pin "2") (pinfunction "2_2") (pintype "passive"))
    )
    (net (code "165") (name "Net-(Q3-PadE)") (class "Default")
      (node (ref "Q3") (pin "E") (pinfunction "E_E") (pintype "passive"))
      (node (ref "R47") (pin "2") (pinfunction "2_2") (pintype "passive"))
    )
    (net (code "166") (name "Net-(Q4-B)") (class "Default")
      (node (ref "C47") (pin "2") (pinfunction "2_2") (pintype "passive"))
      (node (ref "Q4") (pin "2") (pinfunction "B_2") (pintype "passive"))
      (node (ref "R64") (pin "1") (pinfunction "1_1") (pintype "passive"))
      (node (ref "R65") (pin "1") (pinfunction "1_1") (pintype "passive"))
    )
    (net (code "167") (name "Net-(Q4-C)") (class "Default")
      (node (ref "Q4") (pin "3") (pinfunction "C_3") (pintype "passive"))
      (node (ref "Q5") (pin "B") (pinfunction "B_B") (pintype "passive"))
      (node (ref "Q6") (pin "B") (pinfunction "B_B") (pintype "passive"))
      (node (ref "R66") (pin "2") (pinfunction "2_2") (pintype "passive"))
    )
    (net (code "168") (name "Net-(U$1Y-EDGE)") (class "Default")
      (node (ref "C55") (pin "2") (pinfunction "2_2") (pintype "passive"))
      (node (ref "U$1") (pin "4B") (pinfunction "EDGE_4B") (pintype "bidirectional"))
    )
    (net (code "169") (name "Net-(VIDEO(RF)-TP)") (class "Default")
      (node (ref "C42") (pin "2") (pinfunction "2_2") (pintype "passive"))
      (node (ref "R60") (pin "1") (pinfunction "1_1") (pintype "passive"))
      (node (ref "VIDEO(RF)") (pin "1") (pinfunction "TP_1") (pintype "input"))
    )
    (net (code "170") (name "V+") (class "Default")
      (node (ref "7805") (pin "IN") (pinfunction "IN_IN") (pintype "input"))
      (node (ref "C2") (pin "+") (pinfunction "+_+") (pintype "passive"))
      (node (ref "C3") (pin "2") (pinfunction "2_2") (pintype "passive"))
      (node (ref "D22") (pin "A") (pinfunction "A_A") (pintype "bidirectional"))
      (node (ref "JP2") (pin "3") (pinfunction "3_3") (pintype "passive"))
      (node (ref "Q5") (pin "C") (pinfunction "C_C") (pintype "passive"))
      (node (ref "R66") (pin "1") (pinfunction "1_1") (pintype "passive"))
      (node (ref "U$1") (pin "4A") (pinfunction "EDGE_4A") (pintype "bidirectional"))
      (node (ref "X2") (pin "TIP") (pinfunction "TIP_TIP") (pintype "passive"))
    )
    (net (code "171") (name "VDD") (class "Default")
      (node (ref "C23") (pin "1") (pinfunction "1_1") (pintype "passive"))
      (node (ref "C25") (pin "1") (pinfunction "1_1") (pintype "passive"))
      (node (ref "C28") (pin "1") (pinfunction "1_1") (pintype "passive"))
      (node (ref "C30") (pin "1") (pinfunction "1_1") (pintype "passive"))
      (node (ref "IC13") (pin "8") (pinfunction "VDD_8") (pintype "power_in"))
      (node (ref "IC14") (pin "8") (pinfunction "VDD_8") (pintype "power_in"))
      (node (ref "IC15") (pin "8") (pinfunction "VDD_8") (pintype "power_in"))
      (node (ref "IC16") (pin "8") (pinfunction "VDD_8") (pintype "power_in"))
      (node (ref "IC17") (pin "8") (pinfunction "VDD_8") (pintype "power_in"))
      (node (ref "IC18") (pin "8") (pinfunction "VDD_8") (pintype "power_in"))
      (node (ref "IC19") (pin "8") (pinfunction "VDD_8") (pintype "power_in"))
      (node (ref "IC20") (pin "8") (pinfunction "VDD_8") (pintype "power_in"))
      (node (ref "JP2") (pin "2") (pinfunction "2_2") (pintype "passive"))
    )
    (net (code "172") (name "unconnected-(IC3-~{50}{slash}60HZ-Pad1)") (class "Default")
      (node (ref "IC3") (pin "1") (pinfunction "~{50}/60HZ_1") (pintype "input"))
    )
    (net (code "173") (name "unconnected-(IC4A-CLK-Pad3)") (class "Default")
      (node (ref "IC4") (pin "3") (pinfunction "CLK_3") (pintype "input"))
    )
    (net (code "174") (name "unconnected-(IC4A-CLR-Pad1)") (class "Default")
      (node (ref "IC4") (pin "1") (pinfunction "CLR_1") (pintype "input"))
    )
    (net (code "175") (name "unconnected-(IC4A-D-Pad2)") (class "Default")
      (node (ref "IC4") (pin "2") (pinfunction "D_2") (pintype "input"))
    )
    (net (code "176") (name "unconnected-(IC4A-PRE-Pad4)") (class "Default")
      (node (ref "IC4") (pin "4") (pinfunction "PRE_4") (pintype "input"))
    )
    (net (code "177") (name "unconnected-(IC4A-Q-Pad5)") (class "Default")
      (node (ref "IC4") (pin "5") (pinfunction "Q_5") (pintype "output"))
    )
    (net (code "178") (name "unconnected-(IC4A-~{Q}-Pad6)") (class "Default")
      (node (ref "IC4") (pin "6") (pinfunction "~{Q}_6") (pintype "output"))
    )
    (net (code "179") (name "unconnected-(IC5B-~{Q}-Pad8)") (class "Default")
      (node (ref "IC5") (pin "8") (pinfunction "~{Q}_8") (pintype "output"))
    )
    (net (code "180") (name "unconnected-(IC6A-1A-Pad2)") (class "Default")
      (node (ref "IC6") (pin "2") (pinfunction "1A_2") (pintype "input"))
    )
    (net (code "181") (name "unconnected-(IC6A-1B-Pad3)") (class "Default")
      (node (ref "IC6") (pin "3") (pinfunction "1B_3") (pintype "input"))
    )
    (net (code "182") (name "unconnected-(IC6A-1Y-Pad4)") (class "Default")
      (node (ref "IC6") (pin "4") (pinfunction "1Y_4") (pintype "output"))
    )
    (net (code "183") (name "unconnected-(IC6A-3A-Pad11)") (class "Default")
      (node (ref "IC6") (pin "11") (pinfunction "3A_11") (pintype "input"))
    )
    (net (code "184") (name "unconnected-(IC6A-3B-Pad10)") (class "Default")
      (node (ref "IC6") (pin "10") (pinfunction "3B_10") (pintype "input"))
    )
    (net (code "185") (name "unconnected-(IC6A-3Y-Pad9)") (class "Default")
      (node (ref "IC6") (pin "9") (pinfunction "3Y_9") (pintype "output"))
    )
    (net (code "186") (name "unconnected-(IC9A-1A-Pad2)") (class "Default")
      (node (ref "IC9") (pin "2") (pinfunction "1A_2") (pintype "input"))
    )
    (net (code "187") (name "unconnected-(IC9A-1B-Pad3)") (class "Default")
      (node (ref "IC9") (pin "3") (pinfunction "1B_3") (pintype "input"))
    )
    (net (code "188") (name "unconnected-(IC9A-1Y-Pad4)") (class "Default")
      (node (ref "IC9") (pin "4") (pinfunction "1Y_4") (pintype "output"))
    )
    (net (code "189") (name "unconnected-(IC12-CHA_O-Pad11)") (class "Default")
      (node (ref "IC12") (pin "11") (pinfunction "CHA_O_11") (pintype "input"))
    )
    (net (code "190") (name "unconnected-(L1B-S1-PadS2)") (class "Default")
      (node (ref "L1") (pin "S2") (pinfunction "S1_S2") (pintype "passive"))
    )
    (net (code "191") (name "unconnected-(L1B-S2-PadS1)") (class "Default")
      (node (ref "L1") (pin "S1") (pinfunction "S2_S1") (pintype "passive"))
    )
    (net (code "192") (name "unconnected-(U$1AX-EDGE-Pad28B)") (class "Default")
      (node (ref "U$1") (pin "28B") (pinfunction "EDGE_28B") (pintype "bidirectional"))
    )
    (net (code "193") (name "unconnected-(U$1F-EDGE-Pad15A)") (class "Default")
      (node (ref "U$1") (pin "15A") (pinfunction "EDGE_15A") (pintype "bidirectional"))
    )
    (net (code "194") (name "unconnected-(U$1G-EDGE-Pad16A)") (class "Default")
      (node (ref "U$1") (pin "16A") (pinfunction "EDGE_16A") (pintype "bidirectional"))
    )
    (net (code "195") (name "unconnected-(U$1H-EDGE-Pad17A)") (class "Default")
      (node (ref "U$1") (pin "17A") (pinfunction "EDGE_17A") (pintype "bidirectional"))
    )
    (net (code "196") (name "unconnected-(U$1I-EDGE-Pad18A)") (class "Default")
      (node (ref "U$1") (pin "18A") (pinfunction "EDGE_18A") (pintype "bidirectional"))
    )
    (net (code "197") (name "unconnected-(X2-PadNC)") (class "Default")
      (node (ref "X2") (pin "NC") (pinfunction "NC_NC") (pintype "passive"))
    )
  )
)
